# TFG_board_01.net
KiCad netlist of a schematic drawn in EAGLE
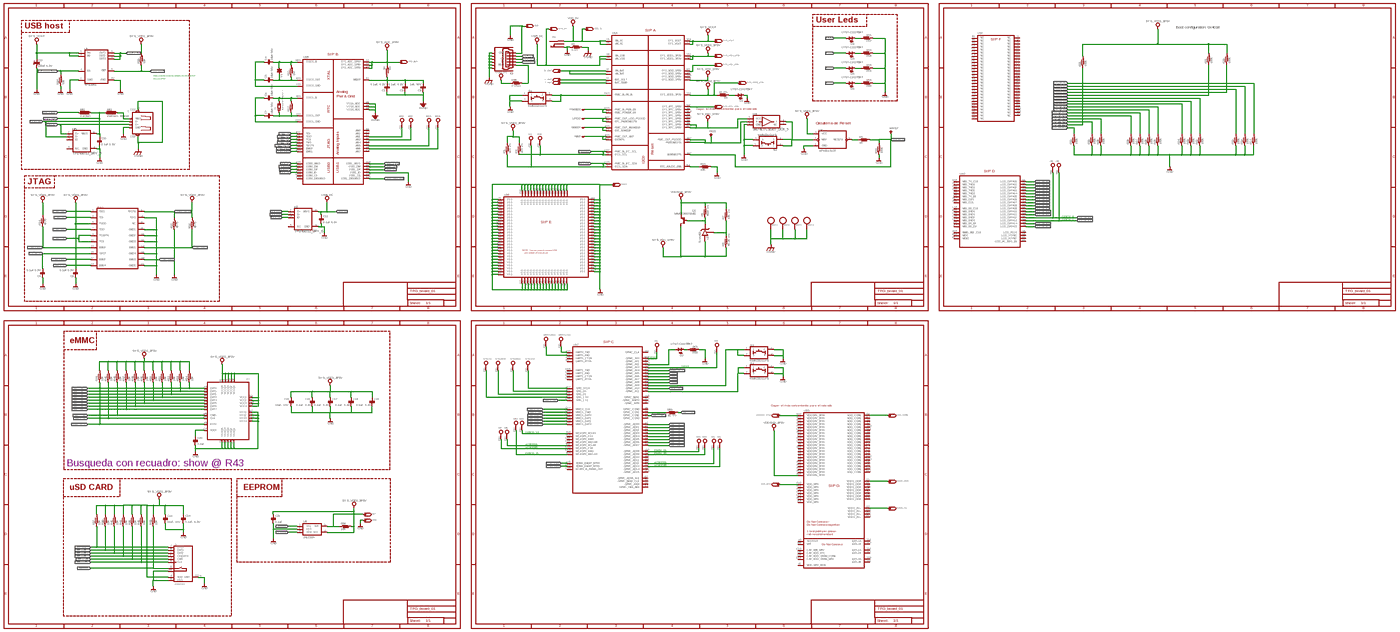
[diagram p0: schematic, sheet 1, overview]
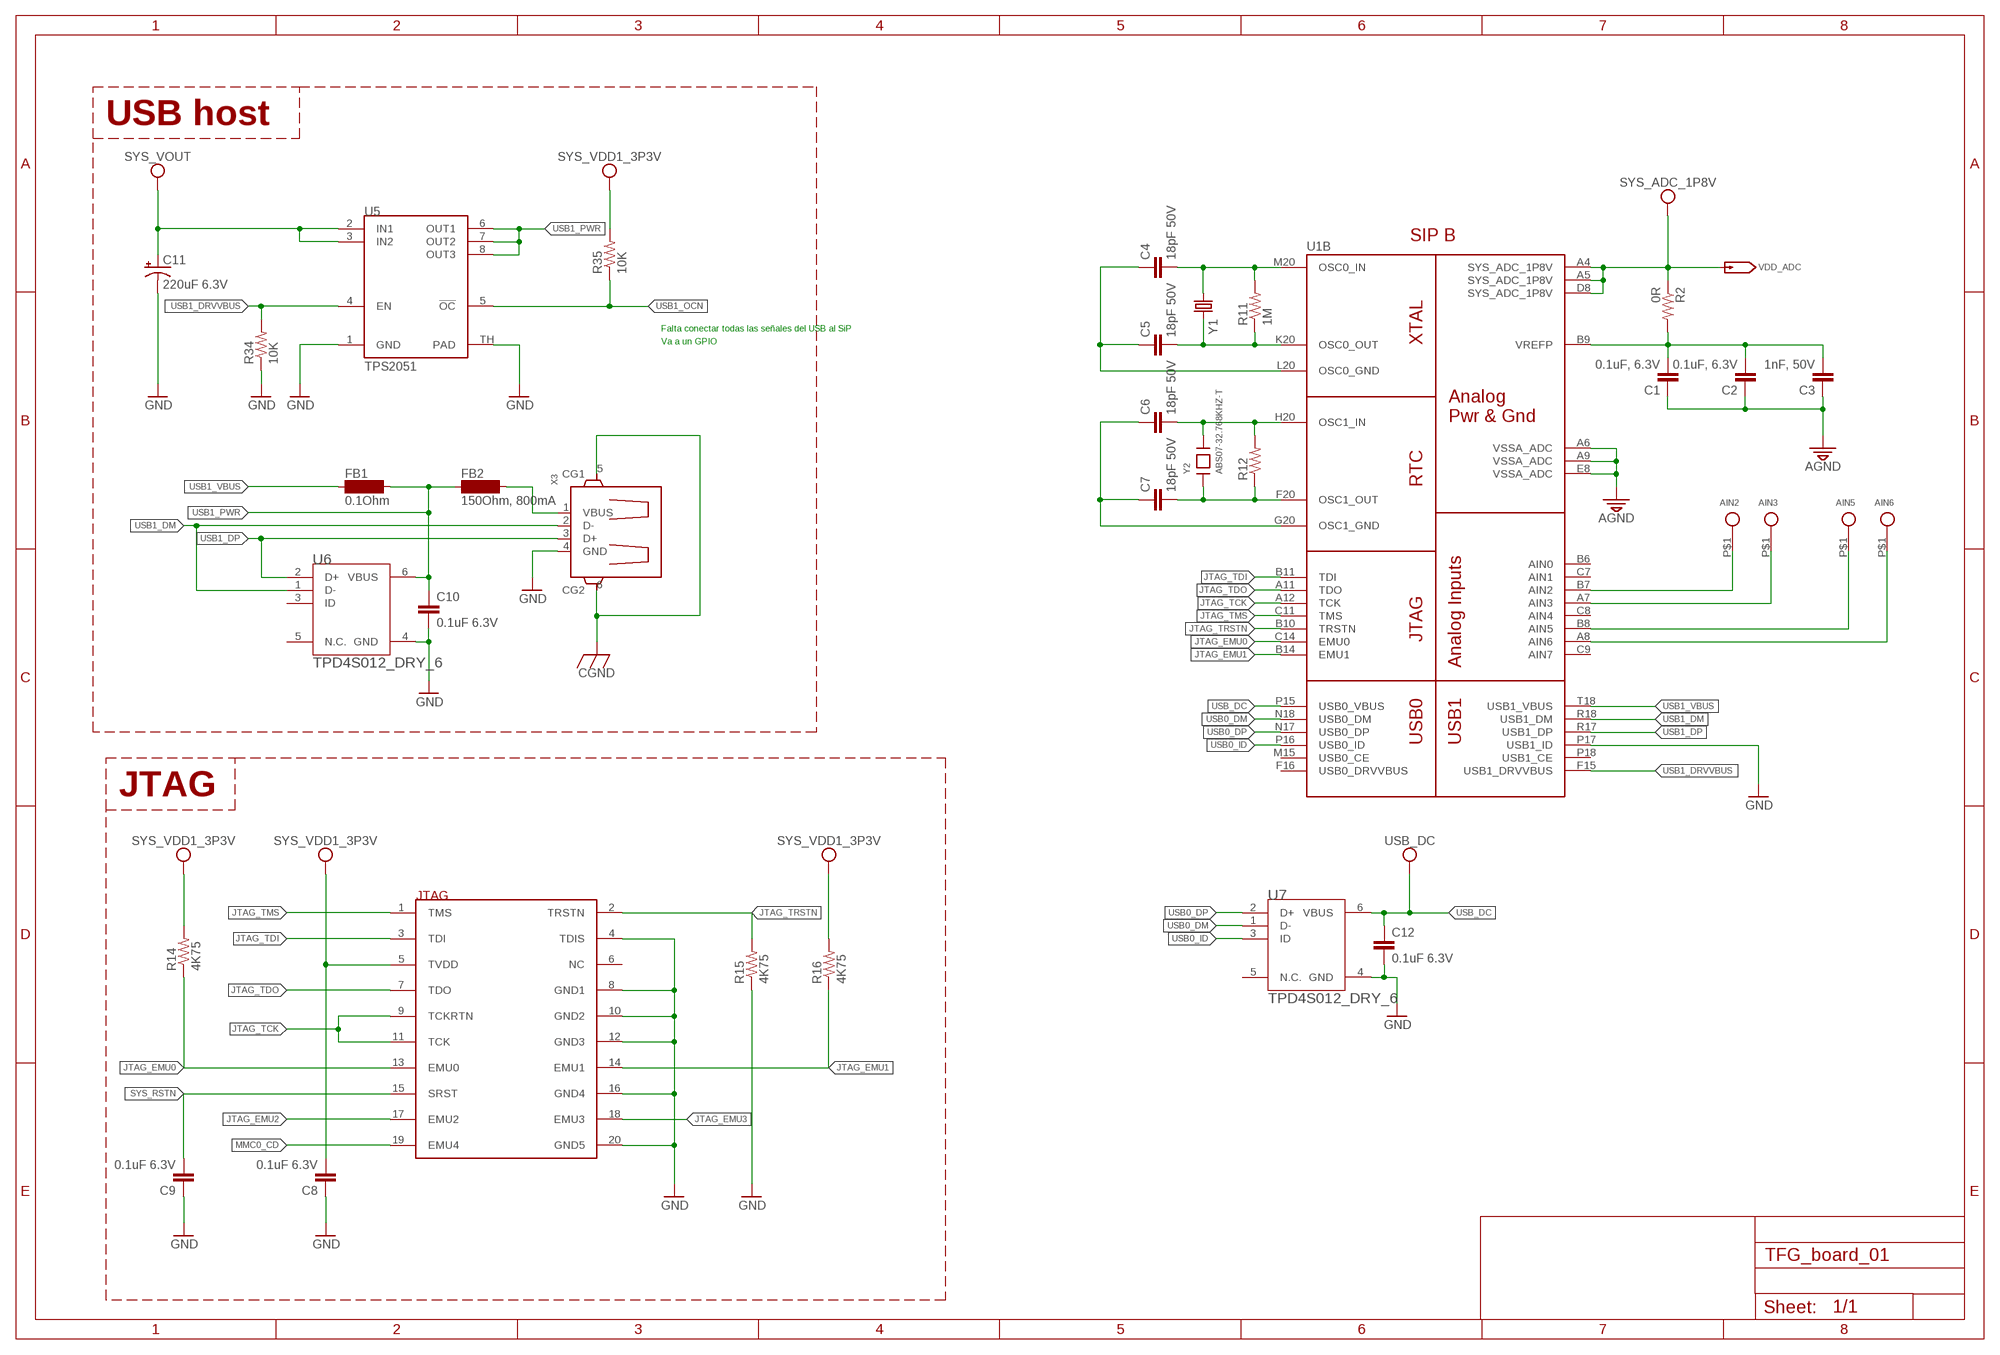
[diagram p1: schematic, sheet 1, part 1 of 7]
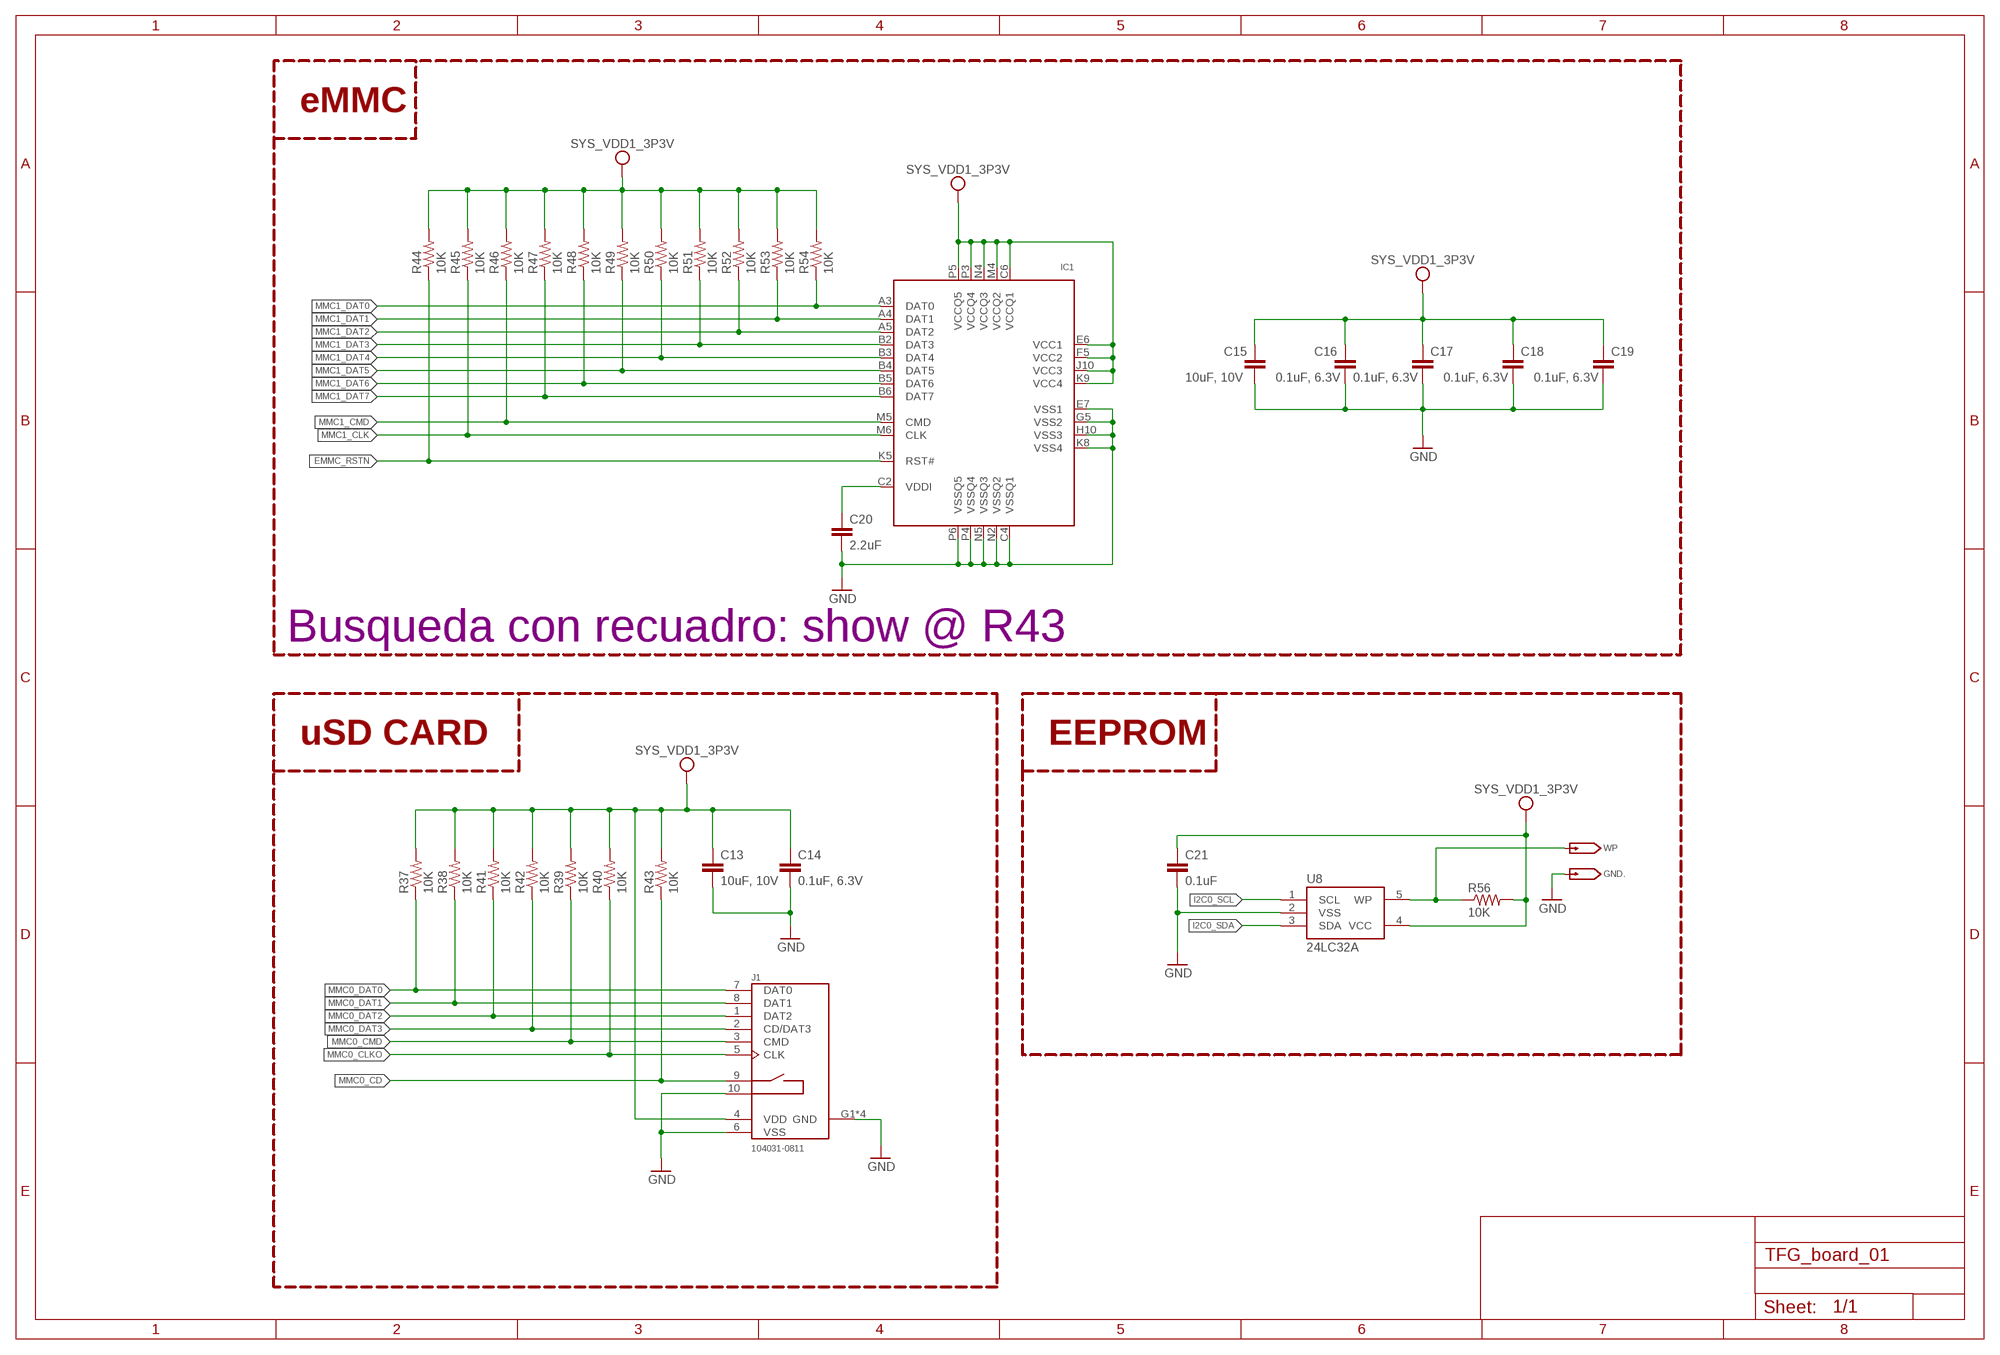
[diagram p2: schematic, sheet 1, part 2 of 7]
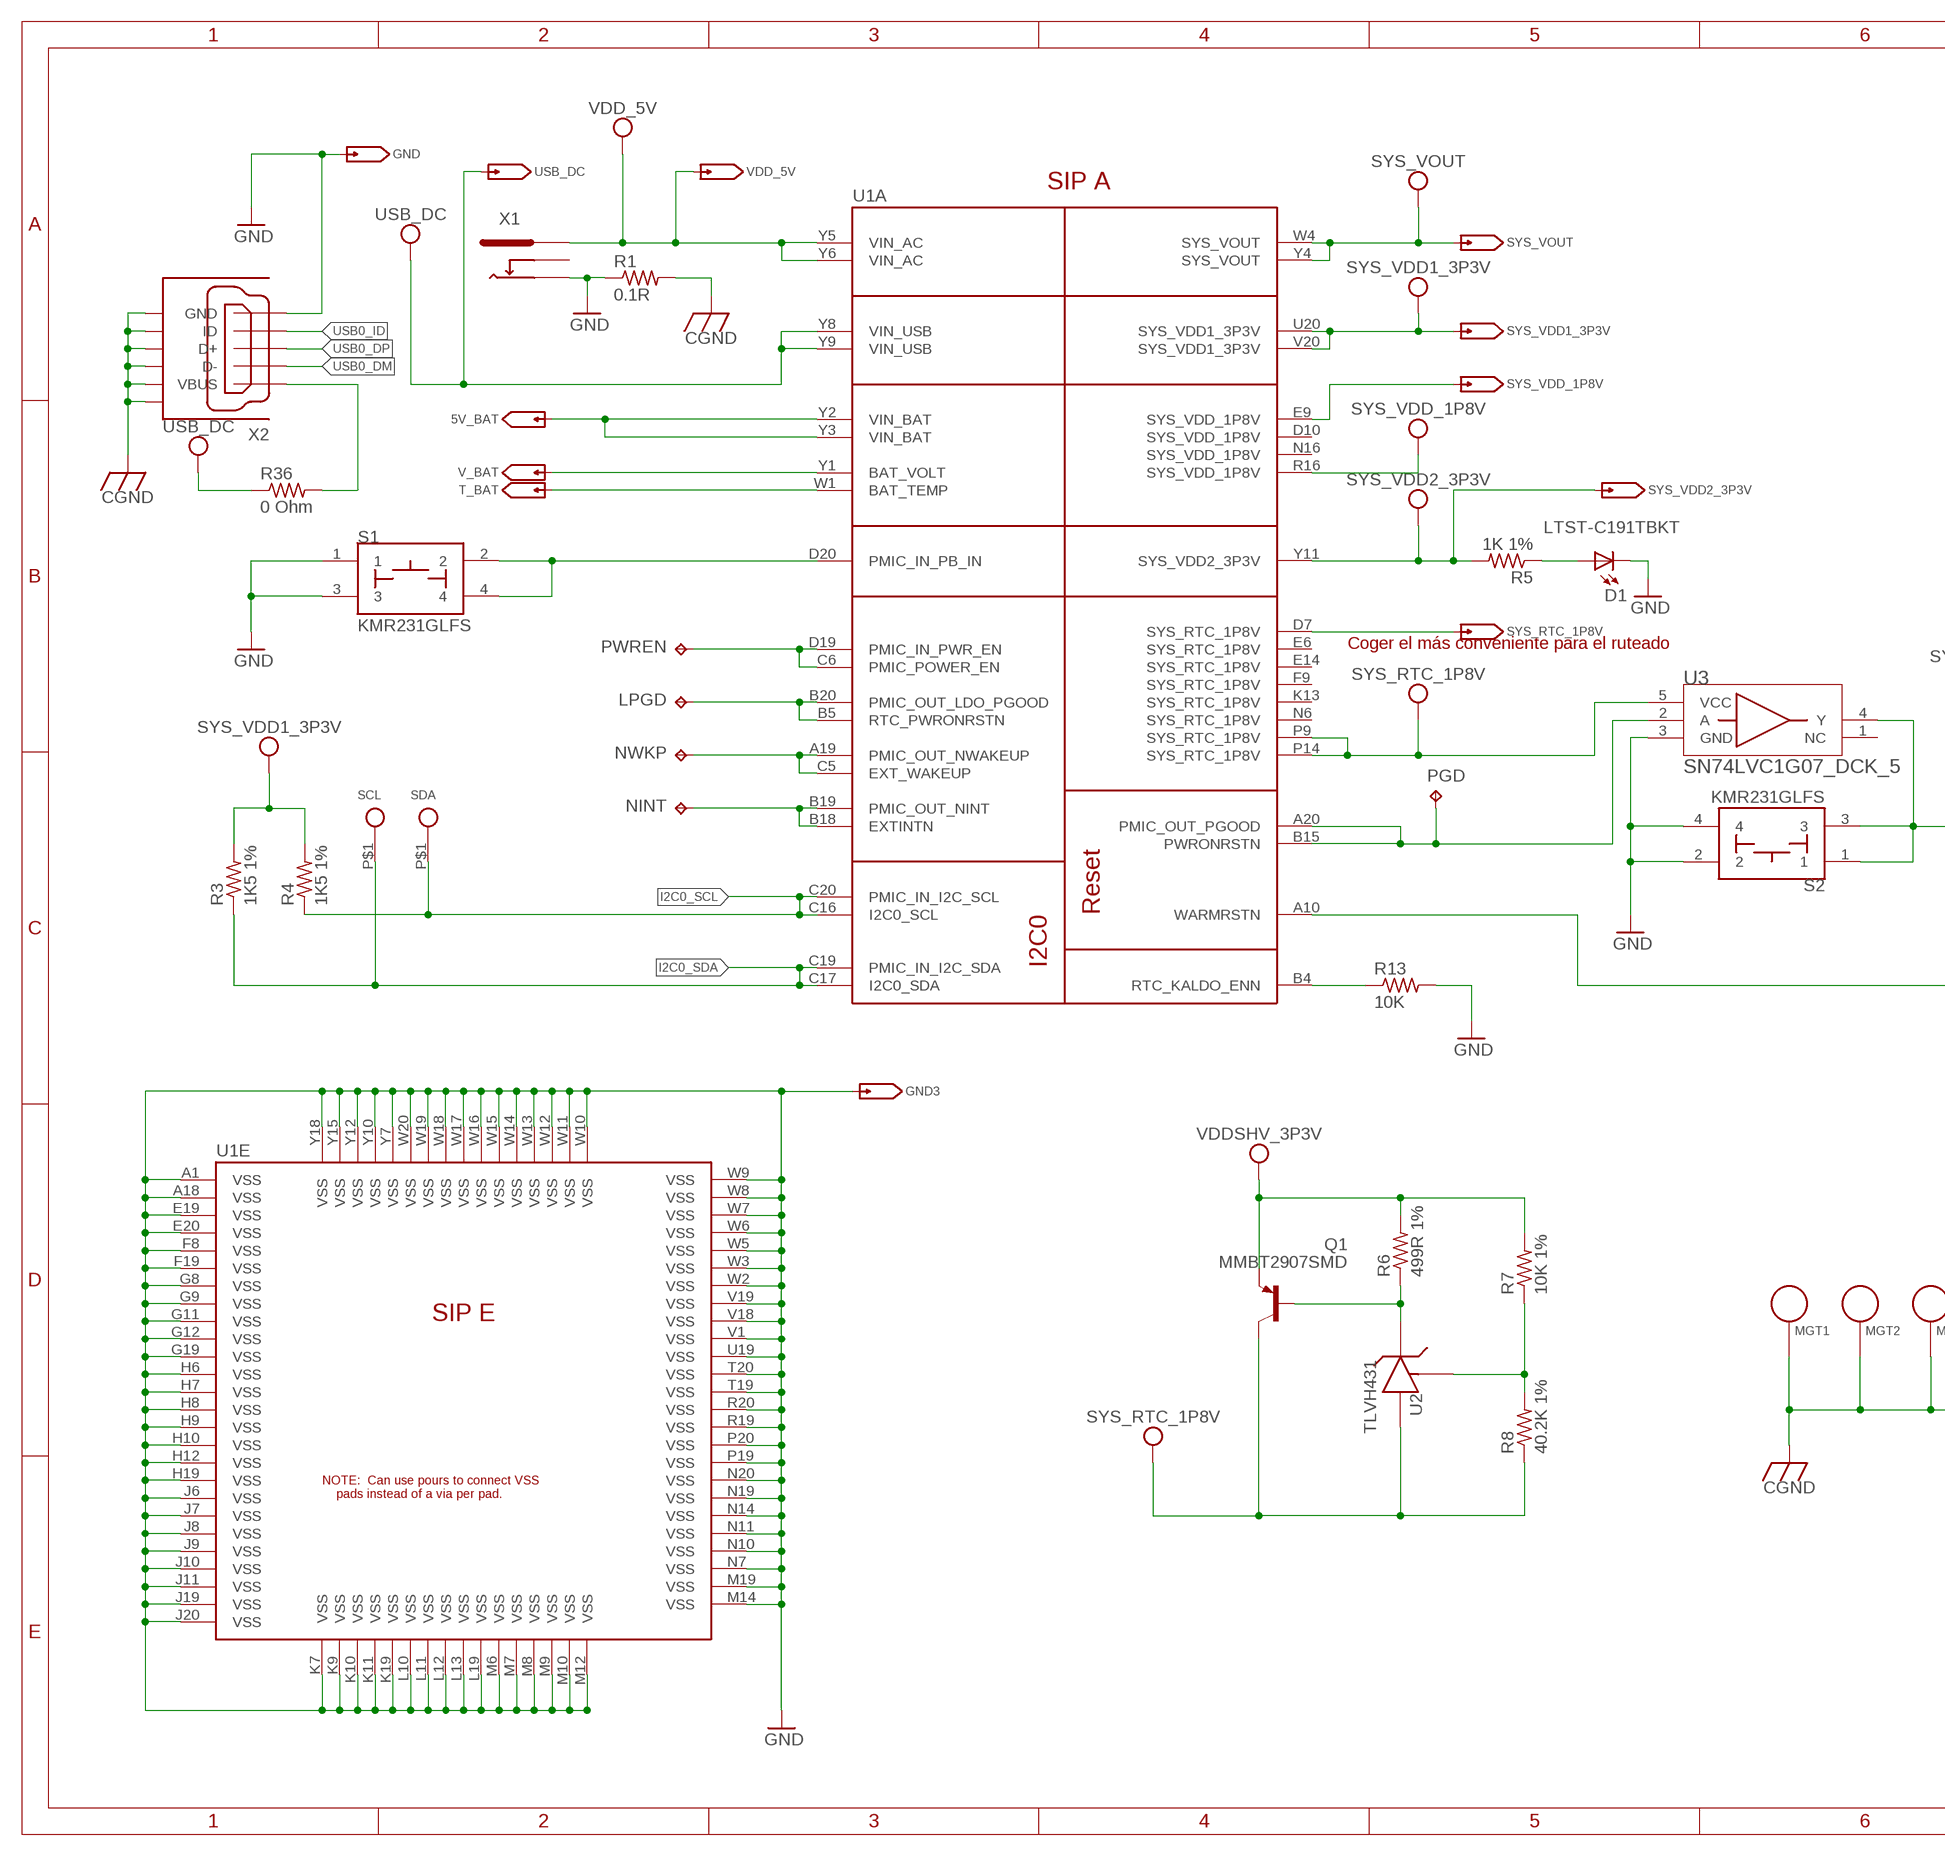
[diagram p3: schematic, sheet 1, part 3 of 7]
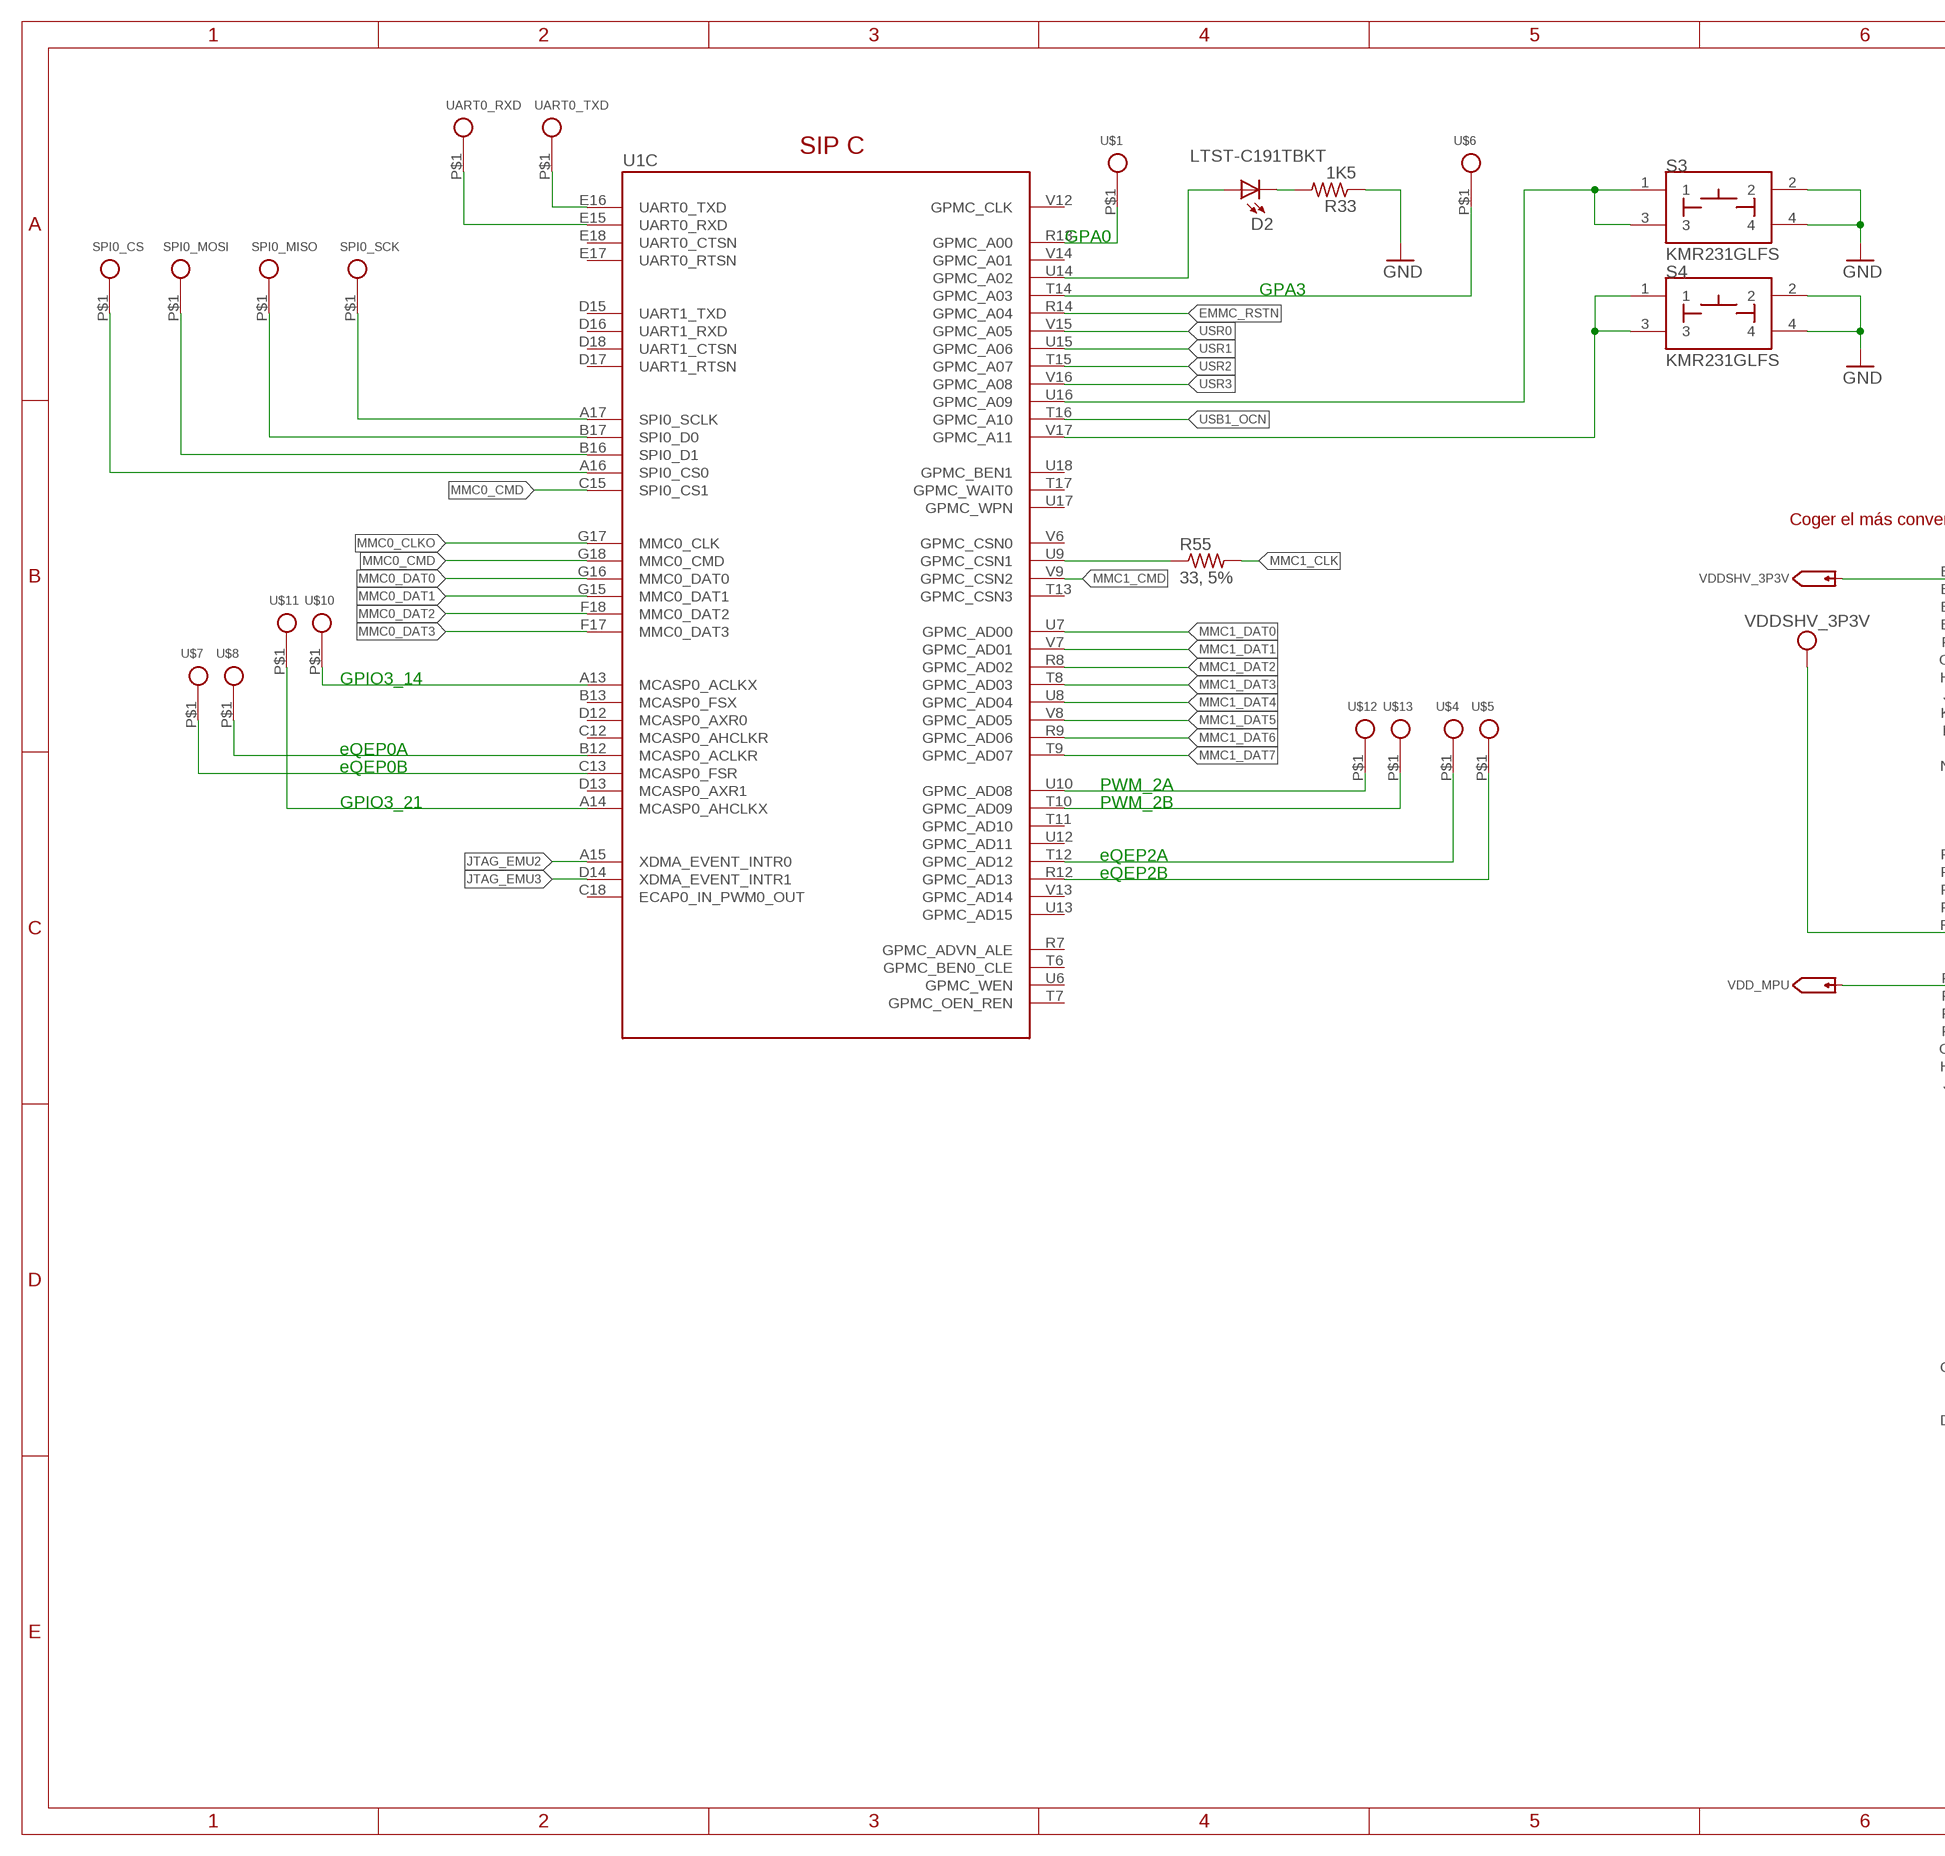
[diagram p4: schematic, sheet 1, part 4 of 7]
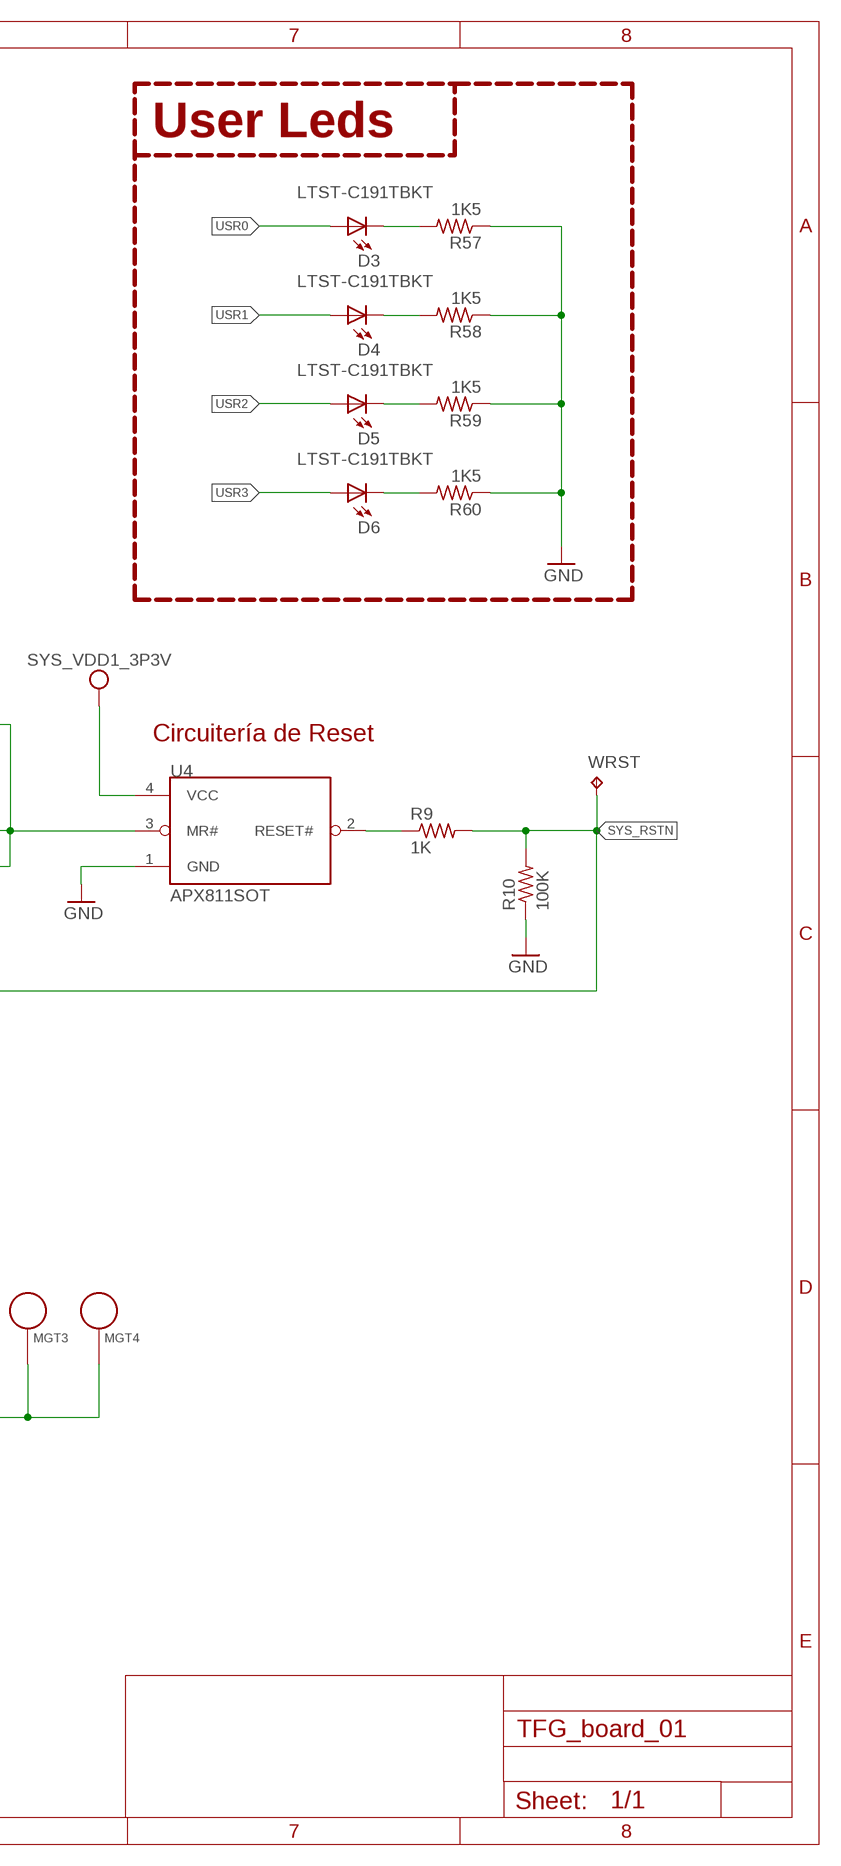
[diagram p5: schematic, sheet 1, part 5 of 7]
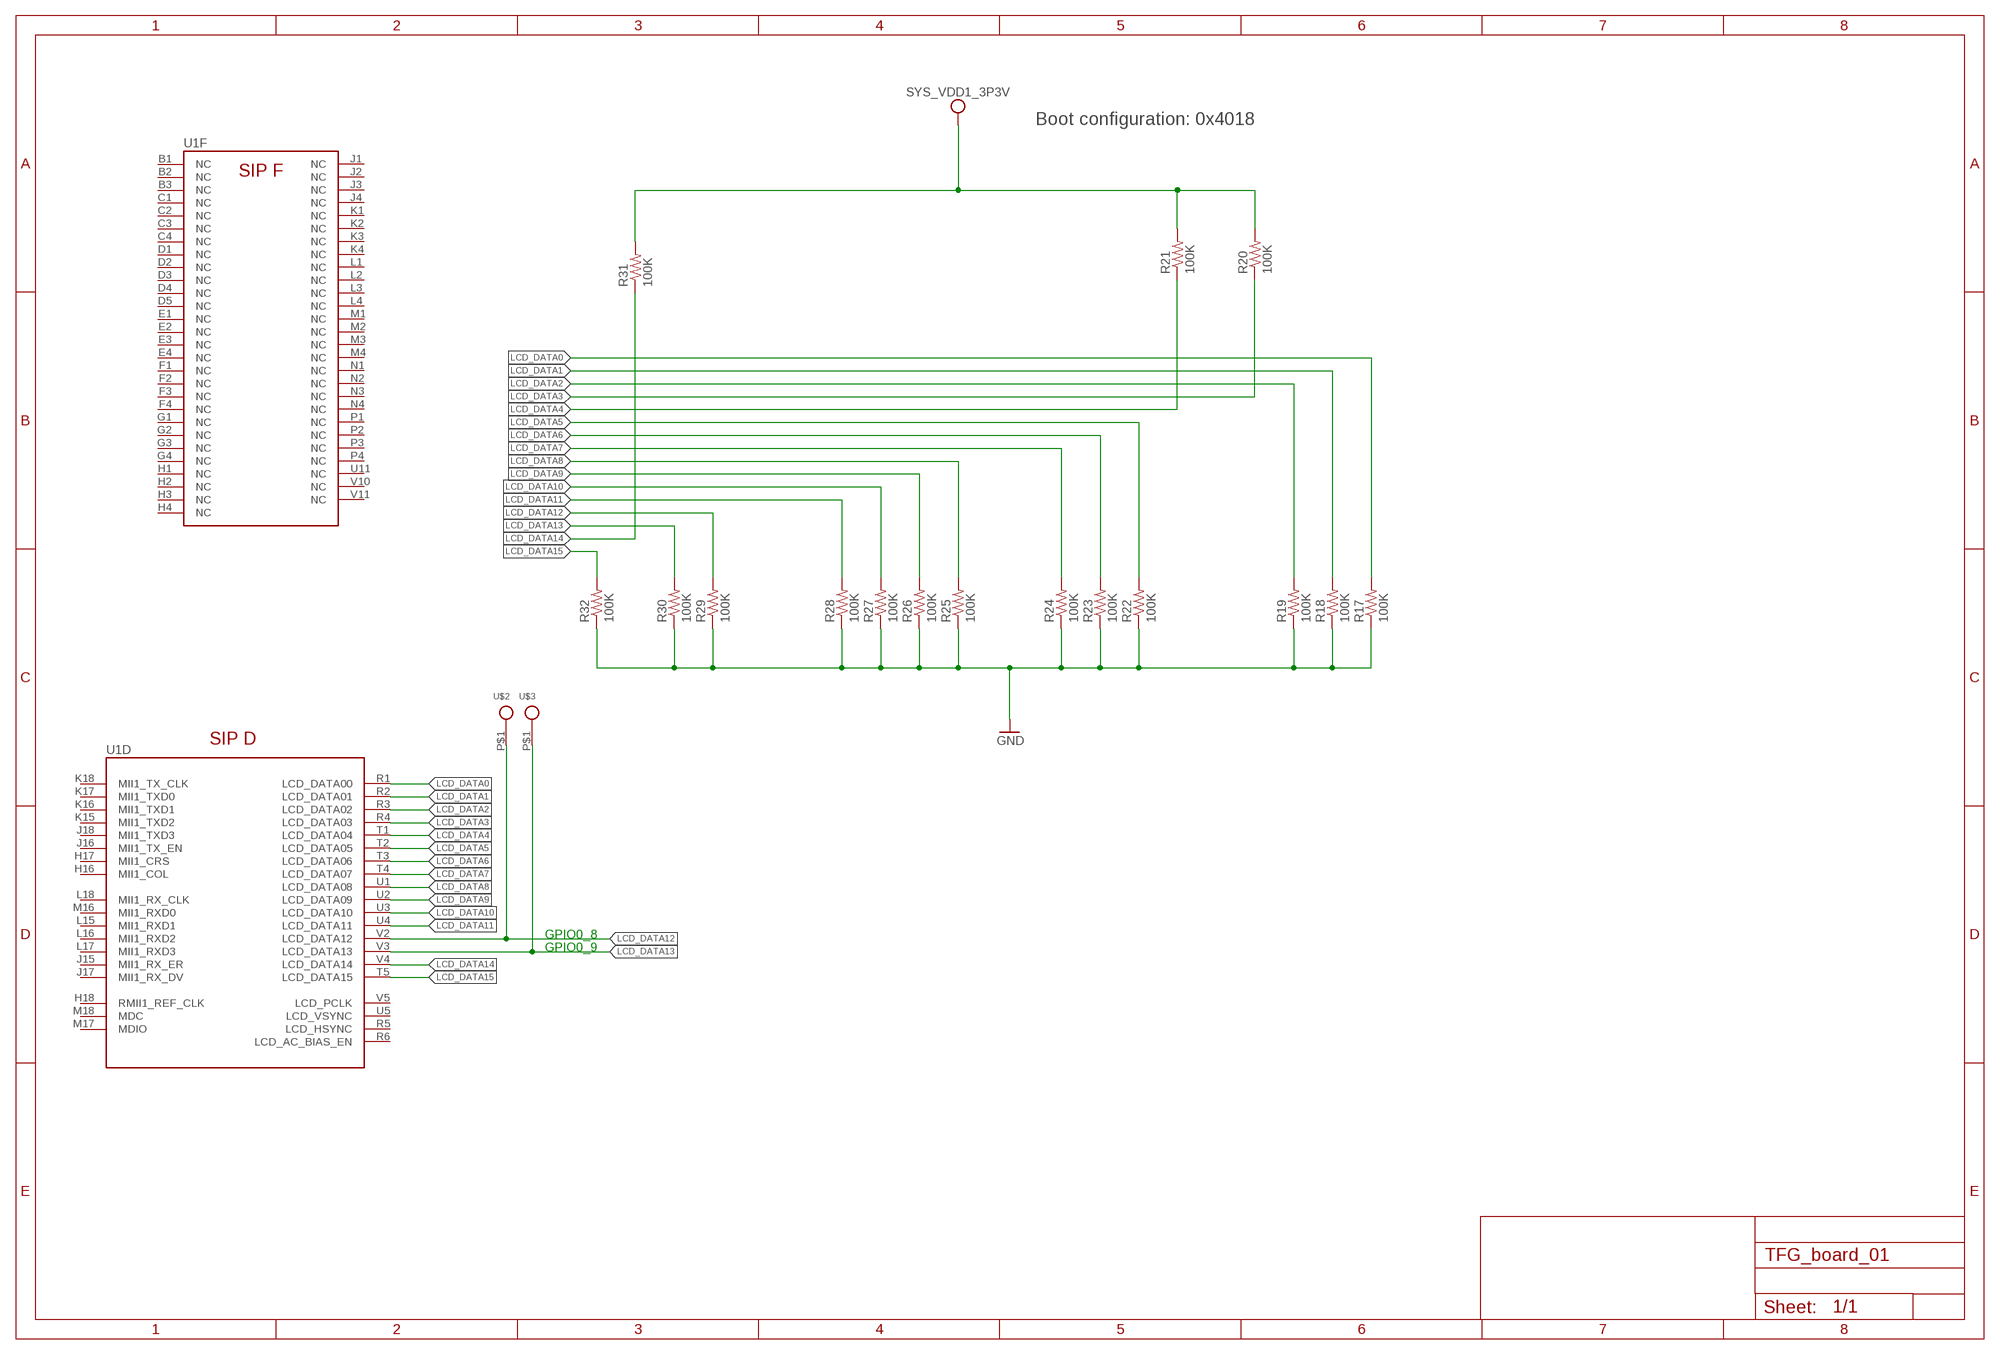
[diagram p6: schematic, sheet 1, part 6 of 7]
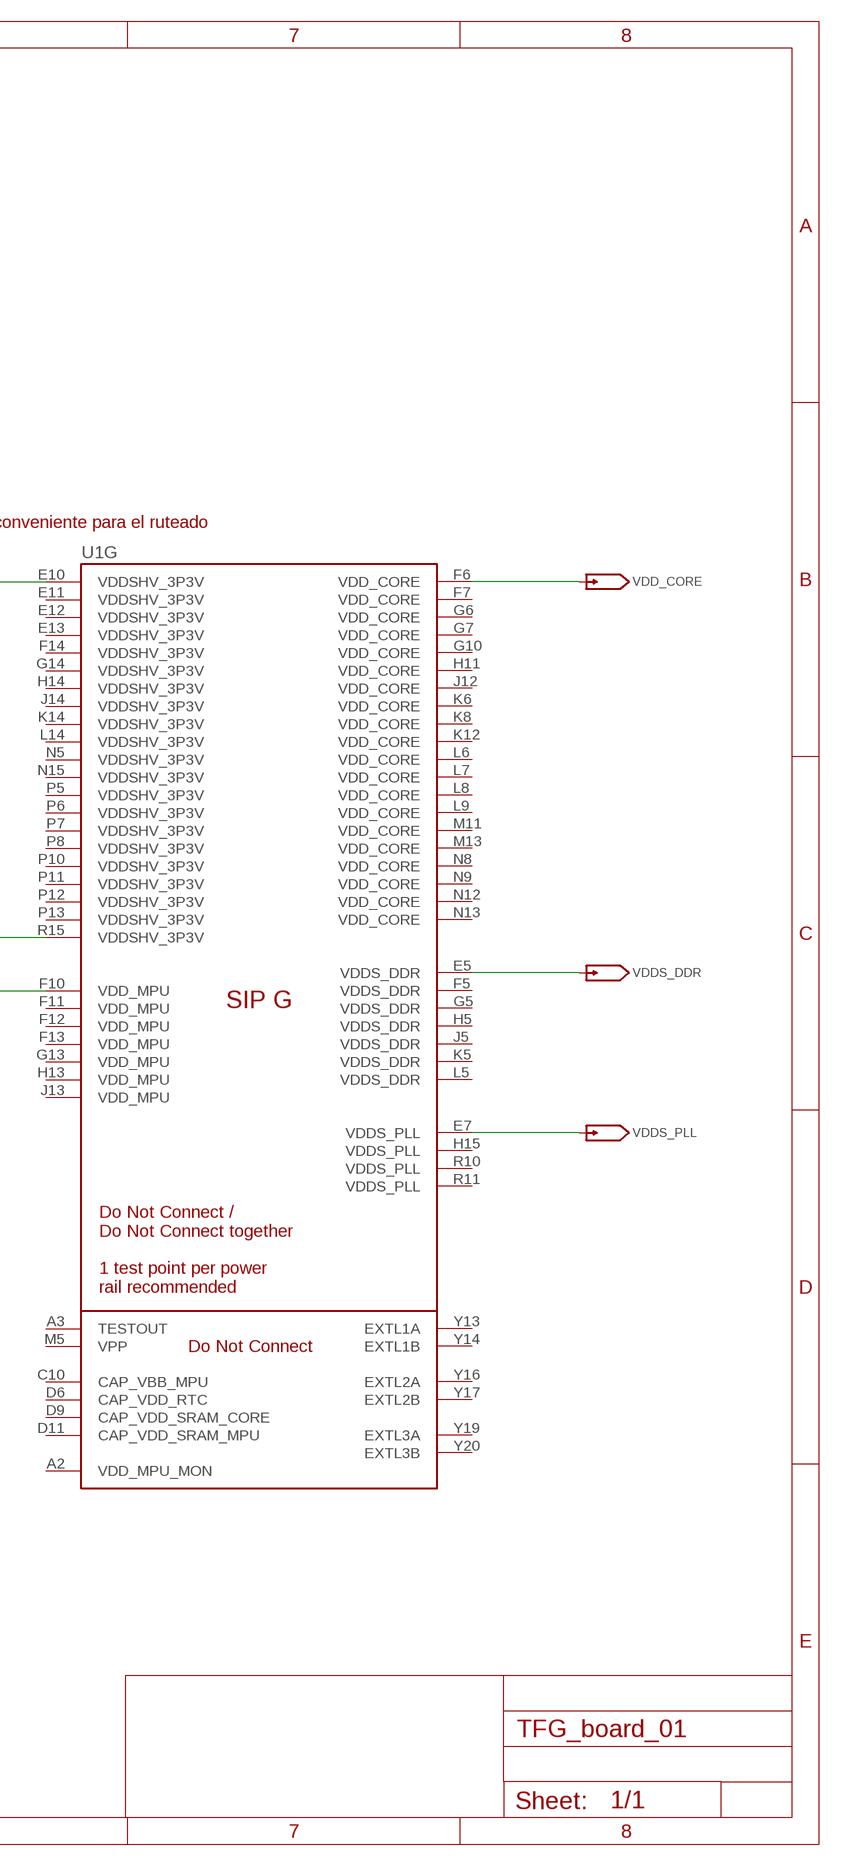
[diagram p7: schematic, sheet 1, part 7 of 7]

(export (version "E")
  (design (tool "Eeschema 10.0.6"))
  (components
    (comp (ref "5V_BAT")
      (value "TESTPAD/W_HOLE_1X1")
      (footprint "eagle-import:TESTPAD_W_HOLE_1X1")
      (libsource (lib "eagle-import") (part "TESTPAD/W_HOLE_1X1"))
    )
    (comp (ref "AIN2")
      (value "HOLE")
      (footprint "eagle-import:HOLE")
      (libsource (lib "eagle-import") (part "HOLE"))
    )
    (comp (ref "AIN3")
      (value "HOLE")
      (footprint "eagle-import:HOLE")
      (libsource (lib "eagle-import") (part "HOLE"))
    )
    (comp (ref "AIN5")
      (value "HOLE")
      (footprint "eagle-import:HOLE")
      (libsource (lib "eagle-import") (part "HOLE"))
    )
    (comp (ref "AIN6")
      (value "HOLE")
      (footprint "eagle-import:HOLE")
      (libsource (lib "eagle-import") (part "HOLE"))
    )
    (comp (ref "C1")
      (value "0.1uF, 6.3V")
      (footprint "eagle-import:C0402")
      (libsource (lib "eagle-import") (part "CC0402"))
    )
    (comp (ref "C2")
      (value "0.1uF, 6.3V")
      (footprint "eagle-import:C0402")
      (libsource (lib "eagle-import") (part "CC0402"))
    )
    (comp (ref "C3")
      (value "1nF, 50V")
      (footprint "eagle-import:C0402")
      (libsource (lib "eagle-import") (part "CC0402"))
    )
    (comp (ref "C4")
      (value "18pF 50V")
      (footprint "eagle-import:C0402")
      (libsource (lib "eagle-import") (part "CC0402"))
    )
    (comp (ref "C5")
      (value "18pF 50V")
      (footprint "eagle-import:C0402")
      (libsource (lib "eagle-import") (part "CC0402"))
    )
    (comp (ref "C6")
      (value "18pF 50V")
      (footprint "eagle-import:C0402")
      (libsource (lib "eagle-import") (part "CC0402"))
    )
    (comp (ref "C7")
      (value "18pF 50V")
      (footprint "eagle-import:C0402")
      (libsource (lib "eagle-import") (part "CC0402"))
    )
    (comp (ref "C8")
      (value "0.1uF 6.3V")
      (footprint "eagle-import:C0402")
      (libsource (lib "eagle-import") (part "CC0402"))
    )
    (comp (ref "C9")
      (value "0.1uF 6.3V")
      (footprint "eagle-import:C0402")
      (libsource (lib "eagle-import") (part "CC0402"))
    )
    (comp (ref "C10")
      (value "0.1uF 6.3V")
      (footprint "eagle-import:C0402")
      (libsource (lib "eagle-import") (part "OSD3358_BAS_RefDesignParts_L2_CC0402"))
    )
    (comp (ref "C11")
      (value "220uF 6.3V")
      (footprint "eagle-import:B_3528-21R")
      (libsource (lib "eagle-import") (part "CPOL-USB/3528-21R"))
    )
    (comp (ref "C12")
      (value "0.1uF 6.3V")
      (footprint "eagle-import:C0402")
      (libsource (lib "eagle-import") (part "OSD3358_BAS_RefDesignParts_L2_CC0402"))
    )
    (comp (ref "C13")
      (value "10uF, 10V")
      (footprint "eagle-import:C0805")
      (libsource (lib "eagle-import") (part "OSD3358_BAS_RefDesignParts_L2_CC0805"))
    )
    (comp (ref "C14")
      (value "0.1uF, 6.3V")
      (footprint "eagle-import:C0402")
      (libsource (lib "eagle-import") (part "OSD3358_BAS_RefDesignParts_L2_CC0402"))
    )
    (comp (ref "C15")
      (value "10uF, 10V")
      (footprint "eagle-import:C0805")
      (libsource (lib "eagle-import") (part "OSD3358_BAS_RefDesignParts_L2_CC0805"))
    )
    (comp (ref "C16")
      (value "0.1uF, 6.3V")
      (footprint "eagle-import:C0402")
      (libsource (lib "eagle-import") (part "OSD3358_BAS_RefDesignParts_L2_CC0402"))
    )
    (comp (ref "C17")
      (value "0.1uF, 6.3V")
      (footprint "eagle-import:C0402")
      (libsource (lib "eagle-import") (part "OSD3358_BAS_RefDesignParts_L2_CC0402"))
    )
    (comp (ref "C18")
      (value "0.1uF, 6.3V")
      (footprint "eagle-import:C0402")
      (libsource (lib "eagle-import") (part "OSD3358_BAS_RefDesignParts_L2_CC0402"))
    )
    (comp (ref "C19")
      (value "0.1uF, 6.3V")
      (footprint "eagle-import:C0402")
      (libsource (lib "eagle-import") (part "OSD3358_BAS_RefDesignParts_L2_CC0402"))
    )
    (comp (ref "C20")
      (value "2.2uF")
      (footprint "eagle-import:C0402")
      (libsource (lib "eagle-import") (part "OSD3358_BAS_RefDesignParts_L2_CC0402"))
    )
    (comp (ref "C21")
      (value "0.1uF")
      (footprint "eagle-import:C0402")
      (libsource (lib "eagle-import") (part "OSD3358_BAS_RefDesignParts_L2_CC0402"))
    )
    (comp (ref "D1")
      (value "LTST-C191TBKT")
      (footprint "eagle-import:EIA-STD")
      (libsource (lib "eagle-import") (part "LTST-C191TBKTLED_EIA-STD"))
    )
    (comp (ref "D2")
      (value "LTST-C191TBKT")
      (footprint "eagle-import:EIA-STD")
      (libsource (lib "eagle-import") (part "LTST-C191TBKTLED_EIA-STD"))
    )
    (comp (ref "D3")
      (value "LTST-C191TBKT")
      (footprint "eagle-import:EIA-STD")
      (libsource (lib "eagle-import") (part "LTST-C191TBKTLED_EIA-STD"))
    )
    (comp (ref "D4")
      (value "LTST-C191TBKT")
      (footprint "eagle-import:EIA-STD")
      (libsource (lib "eagle-import") (part "LTST-C191TBKTLED_EIA-STD"))
    )
    (comp (ref "D5")
      (value "LTST-C191TBKT")
      (footprint "eagle-import:EIA-STD")
      (libsource (lib "eagle-import") (part "LTST-C191TBKTLED_EIA-STD"))
    )
    (comp (ref "D6")
      (value "LTST-C191TBKT")
      (footprint "eagle-import:EIA-STD")
      (libsource (lib "eagle-import") (part "LTST-C191TBKTLED_EIA-STD"))
    )
    (comp (ref "FB1")
      (value "0.1Ohm")
      (footprint "eagle-import:C0805")
      (libsource (lib "eagle-import") (part "MPZ2012S601AT000FB_0805"))
    )
    (comp (ref "FB2")
      (value "150Ohm, 800mA")
      (footprint "eagle-import:C0805")
      (libsource (lib "eagle-import") (part "MPZ2012S601AT000FB_0805"))
    )
    (comp (ref "GND")
      (value "TESTPAD/W_HOLE_1X1")
      (footprint "eagle-import:TESTPAD_W_HOLE_1X1")
      (libsource (lib "eagle-import") (part "TESTPAD/W_HOLE_1X1"))
    )
    (comp (ref "GND.")
      (value "TESTPAD/W_HOLE_1X1")
      (footprint "eagle-import:TESTPAD_W_HOLE_1X1")
      (libsource (lib "eagle-import") (part "OSD3358_BAS_RefDesignParts_L2_TESTPAD/W_HOLE_1X1"))
    )
    (comp (ref "GND3")
      (value "TESTPAD/W_HOLE_1X1")
      (footprint "eagle-import:TESTPAD_W_HOLE_1X1")
      (libsource (lib "eagle-import") (part "TESTPAD/W_HOLE_1X1"))
    )
    (comp (ref "IC1")
      (value "EMMC04G-S100-B08U")
      (footprint "eagle-import:MICRON_EMMC_153")
      (libsource (lib "eagle-import") (part "EMMC04G-S100-B08U"))
    )
    (comp (ref "J1")
      (value "104031-0811")
      (footprint "eagle-import:MOLEX_104031-0811")
      (fields (field (name "MF") "Molex, LLC"))
      (libsource (lib "eagle-import") (part "104031-0811"))
    )
    (comp (ref "JTAG")
      (value "CTI-JTAG")
      (footprint "eagle-import:CTI-JTAG")
      (libsource (lib "eagle-import") (part "CTI-JTAG"))
    )
    (comp (ref "LPGD")
      (value "TPTP15R")
      (footprint "eagle-import:TP15R")
      (libsource (lib "eagle-import") (part "TPTP15R"))
    )
    (comp (ref "MGT1")
      (value "MOUNTING_HOLE")
      (footprint "eagle-import:MOUNTING_HOLE")
      (libsource (lib "eagle-import") (part "MOUNTING_HOLE"))
    )
    (comp (ref "MGT2")
      (value "MOUNTING_HOLE")
      (footprint "eagle-import:MOUNTING_HOLE")
      (libsource (lib "eagle-import") (part "MOUNTING_HOLE"))
    )
    (comp (ref "MGT3")
      (value "MOUNTING_HOLE")
      (footprint "eagle-import:MOUNTING_HOLE")
      (libsource (lib "eagle-import") (part "MOUNTING_HOLE"))
    )
    (comp (ref "MGT4")
      (value "MOUNTING_HOLE")
      (footprint "eagle-import:MOUNTING_HOLE")
      (libsource (lib "eagle-import") (part "MOUNTING_HOLE"))
    )
    (comp (ref "NINT")
      (value "TPTP15R")
      (footprint "eagle-import:TP15R")
      (libsource (lib "eagle-import") (part "TPTP15R"))
    )
    (comp (ref "NWKP")
      (value "TPTP15R")
      (footprint "eagle-import:TP15R")
      (libsource (lib "eagle-import") (part "TPTP15R"))
    )
    (comp (ref "PGD")
      (value "TPTP15R")
      (footprint "eagle-import:TP15R")
      (libsource (lib "eagle-import") (part "TPTP15R"))
    )
    (comp (ref "PWREN")
      (value "TPTP15R")
      (footprint "eagle-import:TP15R")
      (libsource (lib "eagle-import") (part "TPTP15R"))
    )
    (comp (ref "Q1")
      (value "MMBT2907SMD")
      (footprint "eagle-import:SOT23-BEC")
      (libsource (lib "eagle-import") (part "MMBT2907SMD"))
    )
    (comp (ref "R1")
      (value "0.1R")
      (footprint "eagle-import:R0805")
      (libsource (lib "eagle-import") (part "R-US_R0805"))
    )
    (comp (ref "R2")
      (value "0R")
      (footprint "eagle-import:R0402")
      (libsource (lib "eagle-import") (part "R-US_R0402"))
    )
    (comp (ref "R3")
      (value "1K5 1%")
      (footprint "eagle-import:R0402")
      (libsource (lib "eagle-import") (part "R-US_R0402"))
    )
    (comp (ref "R4")
      (value "1K5 1%")
      (footprint "eagle-import:R0402")
      (libsource (lib "eagle-import") (part "R-US_R0402"))
    )
    (comp (ref "R5")
      (value "1K 1%")
      (footprint "eagle-import:R0402")
      (libsource (lib "eagle-import") (part "R-US_R0402"))
    )
    (comp (ref "R6")
      (value "499R 1%")
      (footprint "eagle-import:R0402")
      (libsource (lib "eagle-import") (part "R-US_R0402"))
    )
    (comp (ref "R7")
      (value "10K 1%")
      (footprint "eagle-import:R0402")
      (libsource (lib "eagle-import") (part "R-US_R0402"))
    )
    (comp (ref "R8")
      (value "40.2K 1%")
      (footprint "eagle-import:R0402")
      (libsource (lib "eagle-import") (part "R-US_R0402"))
    )
    (comp (ref "R9")
      (value "1K")
      (footprint "eagle-import:R0402")
      (libsource (lib "eagle-import") (part "R-US_R0402"))
    )
    (comp (ref "R10")
      (value "100K")
      (footprint "eagle-import:R0402")
      (libsource (lib "eagle-import") (part "R-US_R0402"))
    )
    (comp (ref "R11")
      (value "1M")
      (footprint "eagle-import:R0402")
      (libsource (lib "eagle-import") (part "R-US_R0402"))
    )
    (comp (ref "R12")
      (value "R-US_R0402")
      (footprint "eagle-import:R0402")
      (libsource (lib "eagle-import") (part "R-US_R0402"))
    )
    (comp (ref "R13")
      (value "10K")
      (footprint "eagle-import:R0402")
      (libsource (lib "eagle-import") (part "R-US_R0402"))
    )
    (comp (ref "R14")
      (value "4K75")
      (footprint "eagle-import:R0402")
      (libsource (lib "eagle-import") (part "R-US_R0402"))
    )
    (comp (ref "R15")
      (value "4K75")
      (footprint "eagle-import:R0402")
      (libsource (lib "eagle-import") (part "R-US_R0402"))
    )
    (comp (ref "R16")
      (value "4K75")
      (footprint "eagle-import:R0402")
      (libsource (lib "eagle-import") (part "R-US_R0402"))
    )
    (comp (ref "R17")
      (value "100K")
      (footprint "eagle-import:R0402")
      (libsource (lib "eagle-import") (part "R-US_R0402"))
    )
    (comp (ref "R18")
      (value "100K")
      (footprint "eagle-import:R0402")
      (libsource (lib "eagle-import") (part "R-US_R0402"))
    )
    (comp (ref "R19")
      (value "100K")
      (footprint "eagle-import:R0402")
      (libsource (lib "eagle-import") (part "R-US_R0402"))
    )
    (comp (ref "R20")
      (value "100K")
      (footprint "eagle-import:R0402")
      (libsource (lib "eagle-import") (part "R-US_R0402"))
    )
    (comp (ref "R21")
      (value "100K")
      (footprint "eagle-import:R0402")
      (libsource (lib "eagle-import") (part "R-US_R0402"))
    )
    (comp (ref "R22")
      (value "100K")
      (footprint "eagle-import:R0402")
      (libsource (lib "eagle-import") (part "R-US_R0402"))
    )
    (comp (ref "R23")
      (value "100K")
      (footprint "eagle-import:R0402")
      (libsource (lib "eagle-import") (part "R-US_R0402"))
    )
    (comp (ref "R24")
      (value "100K")
      (footprint "eagle-import:R0402")
      (libsource (lib "eagle-import") (part "R-US_R0402"))
    )
    (comp (ref "R25")
      (value "100K")
      (footprint "eagle-import:R0402")
      (libsource (lib "eagle-import") (part "R-US_R0402"))
    )
    (comp (ref "R26")
      (value "100K")
      (footprint "eagle-import:R0402")
      (libsource (lib "eagle-import") (part "R-US_R0402"))
    )
    (comp (ref "R27")
      (value "100K")
      (footprint "eagle-import:R0402")
      (libsource (lib "eagle-import") (part "R-US_R0402"))
    )
    (comp (ref "R28")
      (value "100K")
      (footprint "eagle-import:R0402")
      (libsource (lib "eagle-import") (part "R-US_R0402"))
    )
    (comp (ref "R29")
      (value "100K")
      (footprint "eagle-import:R0402")
      (libsource (lib "eagle-import") (part "R-US_R0402"))
    )
    (comp (ref "R30")
      (value "100K")
      (footprint "eagle-import:R0402")
      (libsource (lib "eagle-import") (part "R-US_R0402"))
    )
    (comp (ref "R31")
      (value "100K")
      (footprint "eagle-import:R0402")
      (libsource (lib "eagle-import") (part "R-US_R0402"))
    )
    (comp (ref "R32")
      (value "100K")
      (footprint "eagle-import:R0402")
      (libsource (lib "eagle-import") (part "R-US_R0402"))
    )
    (comp (ref "R33")
      (value "1K5")
      (footprint "eagle-import:R0402")
      (libsource (lib "eagle-import") (part "R-US_R0402"))
    )
    (comp (ref "R34")
      (value "10K")
      (footprint "eagle-import:R0402")
      (libsource (lib "eagle-import") (part "OSD3358_BAS_RefDesignParts_L2_R-US_R0402"))
    )
    (comp (ref "R35")
      (value "10K")
      (footprint "eagle-import:R0402")
      (libsource (lib "eagle-import") (part "OSD3358_BAS_RefDesignParts_L2_R-US_R0402"))
    )
    (comp (ref "R36")
      (value "0 Ohm")
      (footprint "eagle-import:R0805")
      (libsource (lib "eagle-import") (part "R-US_R0805"))
    )
    (comp (ref "R37")
      (value "10K")
      (footprint "eagle-import:R0402")
      (libsource (lib "eagle-import") (part "R-US_R0402"))
    )
    (comp (ref "R38")
      (value "10K")
      (footprint "eagle-import:R0402")
      (libsource (lib "eagle-import") (part "R-US_R0402"))
    )
    (comp (ref "R39")
      (value "10K")
      (footprint "eagle-import:R0402")
      (libsource (lib "eagle-import") (part "R-US_R0402"))
    )
    (comp (ref "R40")
      (value "10K")
      (footprint "eagle-import:R0402")
      (libsource (lib "eagle-import") (part "R-US_R0402"))
    )
    (comp (ref "R41")
      (value "10K")
      (footprint "eagle-import:R0402")
      (libsource (lib "eagle-import") (part "R-US_R0402"))
    )
    (comp (ref "R42")
      (value "10K")
      (footprint "eagle-import:R0402")
      (libsource (lib "eagle-import") (part "R-US_R0402"))
    )
    (comp (ref "R43")
      (value "10K")
      (footprint "eagle-import:R0402")
      (libsource (lib "eagle-import") (part "R-US_R0402"))
    )
    (comp (ref "R44")
      (value "10K")
      (footprint "eagle-import:R0402")
      (libsource (lib "eagle-import") (part "OSD3358_BAS_RefDesignParts_L2_R-US_R0402"))
    )
    (comp (ref "R45")
      (value "10K")
      (footprint "eagle-import:R0402")
      (libsource (lib "eagle-import") (part "OSD3358_BAS_RefDesignParts_L2_R-US_R0402"))
    )
    (comp (ref "R46")
      (value "10K")
      (footprint "eagle-import:R0402")
      (libsource (lib "eagle-import") (part "OSD3358_BAS_RefDesignParts_L2_R-US_R0402"))
    )
    (comp (ref "R47")
      (value "10K")
      (footprint "eagle-import:R0402")
      (libsource (lib "eagle-import") (part "OSD3358_BAS_RefDesignParts_L2_R-US_R0402"))
    )
    (comp (ref "R48")
      (value "10K")
      (footprint "eagle-import:R0402")
      (libsource (lib "eagle-import") (part "OSD3358_BAS_RefDesignParts_L2_R-US_R0402"))
    )
    (comp (ref "R49")
      (value "10K")
      (footprint "eagle-import:R0402")
      (libsource (lib "eagle-import") (part "OSD3358_BAS_RefDesignParts_L2_R-US_R0402"))
    )
    (comp (ref "R50")
      (value "10K")
      (footprint "eagle-import:R0402")
      (libsource (lib "eagle-import") (part "OSD3358_BAS_RefDesignParts_L2_R-US_R0402"))
    )
    (comp (ref "R51")
      (value "10K")
      (footprint "eagle-import:R0402")
      (libsource (lib "eagle-import") (part "OSD3358_BAS_RefDesignParts_L2_R-US_R0402"))
    )
    (comp (ref "R52")
      (value "10K")
      (footprint "eagle-import:R0402")
      (libsource (lib "eagle-import") (part "OSD3358_BAS_RefDesignParts_L2_R-US_R0402"))
    )
    (comp (ref "R53")
      (value "10K")
      (footprint "eagle-import:R0402")
      (libsource (lib "eagle-import") (part "OSD3358_BAS_RefDesignParts_L2_R-US_R0402"))
    )
    (comp (ref "R54")
      (value "10K")
      (footprint "eagle-import:R0402")
      (libsource (lib "eagle-import") (part "OSD3358_BAS_RefDesignParts_L2_R-US_R0402"))
    )
    (comp (ref "R55")
      (value "33, 5%")
      (footprint "eagle-import:R0402")
      (libsource (lib "eagle-import") (part "OSD3358_BAS_RefDesignParts_L2_R-US_R0402"))
    )
    (comp (ref "R56")
      (value "10K")
      (footprint "eagle-import:R0402")
      (libsource (lib "eagle-import") (part "OSD3358_BAS_RefDesignParts_L2_R-US_R0402"))
    )
    (comp (ref "R57")
      (value "1K5")
      (footprint "eagle-import:R0402")
      (libsource (lib "eagle-import") (part "R-US_R0402"))
    )
    (comp (ref "R58")
      (value "1K5")
      (footprint "eagle-import:R0402")
      (libsource (lib "eagle-import") (part "R-US_R0402"))
    )
    (comp (ref "R59")
      (value "1K5")
      (footprint "eagle-import:R0402")
      (libsource (lib "eagle-import") (part "R-US_R0402"))
    )
    (comp (ref "R60")
      (value "1K5")
      (footprint "eagle-import:R0402")
      (libsource (lib "eagle-import") (part "R-US_R0402"))
    )
    (comp (ref "S1")
      (value "KMR231GLFS")
      (footprint "eagle-import:SW4SMD_63X161LS")
      (libsource (lib "eagle-import") (part "KMR231GLFS"))
    )
    (comp (ref "S2")
      (value "KMR231GLFS")
      (footprint "eagle-import:SW4SMD_63X161LS")
      (libsource (lib "eagle-import") (part "KMR231GLFS"))
    )
    (comp (ref "S3")
      (value "KMR231GLFS")
      (footprint "eagle-import:SW4SMD_63X161LS")
      (libsource (lib "eagle-import") (part "KMR231GLFS"))
    )
    (comp (ref "S4")
      (value "KMR231GLFS")
      (footprint "eagle-import:SW4SMD_63X161LS")
      (libsource (lib "eagle-import") (part "KMR231GLFS"))
    )
    (comp (ref "SCL")
      (value "HOLE")
      (footprint "eagle-import:HOLE")
      (libsource (lib "eagle-import") (part "HOLE"))
    )
    (comp (ref "SDA")
      (value "HOLE")
      (footprint "eagle-import:HOLE")
      (libsource (lib "eagle-import") (part "HOLE"))
    )
    (comp (ref "SPI0_CS")
      (value "HOLE")
      (footprint "eagle-import:HOLE")
      (libsource (lib "eagle-import") (part "HOLE"))
    )
    (comp (ref "SPI0_MISO")
      (value "HOLE")
      (footprint "eagle-import:HOLE")
      (libsource (lib "eagle-import") (part "HOLE"))
    )
    (comp (ref "SPI0_MOSI")
      (value "HOLE")
      (footprint "eagle-import:HOLE")
      (libsource (lib "eagle-import") (part "HOLE"))
    )
    (comp (ref "SPI0_SCK")
      (value "HOLE")
      (footprint "eagle-import:HOLE")
      (libsource (lib "eagle-import") (part "HOLE"))
    )
    (comp (ref "SYS_RTC_1P8V")
      (value "TESTPAD/W_HOLE_1X1")
      (footprint "eagle-import:TESTPAD_W_HOLE_1X1")
      (libsource (lib "eagle-import") (part "TESTPAD/W_HOLE_1X1"))
    )
    (comp (ref "SYS_VDD1_3P3V")
      (value "TESTPAD/W_HOLE_1X1")
      (footprint "eagle-import:TESTPAD_W_HOLE_1X1")
      (libsource (lib "eagle-import") (part "TESTPAD/W_HOLE_1X1"))
    )
    (comp (ref "SYS_VDD2_3P3V")
      (value "TESTPAD/W_HOLE_1X1")
      (footprint "eagle-import:TESTPAD_W_HOLE_1X1")
      (libsource (lib "eagle-import") (part "TESTPAD/W_HOLE_1X1"))
    )
    (comp (ref "SYS_VDD_1P8V")
      (value "TESTPAD/W_HOLE_1X1")
      (footprint "eagle-import:TESTPAD_W_HOLE_1X1")
      (libsource (lib "eagle-import") (part "TESTPAD/W_HOLE_1X1"))
    )
    (comp (ref "SYS_VOUT")
      (value "TESTPAD/W_HOLE_1X1")
      (footprint "eagle-import:TESTPAD_W_HOLE_1X1")
      (libsource (lib "eagle-import") (part "TESTPAD/W_HOLE_1X1"))
    )
    (comp (ref "T_BAT")
      (value "TESTPAD/W_HOLE_1X1")
      (footprint "eagle-import:TESTPAD_W_HOLE_1X1")
      (libsource (lib "eagle-import") (part "TESTPAD/W_HOLE_1X1"))
    )
    (comp (ref "U$1")
      (value "HOLE")
      (footprint "eagle-import:HOLE")
      (libsource (lib "eagle-import") (part "HOLE"))
    )
    (comp (ref "U$2")
      (value "HOLE")
      (footprint "eagle-import:HOLE")
      (libsource (lib "eagle-import") (part "HOLE"))
    )
    (comp (ref "U$3")
      (value "HOLE")
      (footprint "eagle-import:HOLE")
      (libsource (lib "eagle-import") (part "HOLE"))
    )
    (comp (ref "U$4")
      (value "HOLE")
      (footprint "eagle-import:HOLE")
      (libsource (lib "eagle-import") (part "HOLE"))
    )
    (comp (ref "U$5")
      (value "HOLE")
      (footprint "eagle-import:HOLE")
      (libsource (lib "eagle-import") (part "HOLE"))
    )
    (comp (ref "U$6")
      (value "HOLE")
      (footprint "eagle-import:HOLE")
      (libsource (lib "eagle-import") (part "HOLE"))
    )
    (comp (ref "U$7")
      (value "HOLE")
      (footprint "eagle-import:HOLE")
      (libsource (lib "eagle-import") (part "HOLE"))
    )
    (comp (ref "U$8")
      (value "HOLE")
      (footprint "eagle-import:HOLE")
      (libsource (lib "eagle-import") (part "HOLE"))
    )
    (comp (ref "U$10")
      (value "HOLE")
      (footprint "eagle-import:HOLE")
      (libsource (lib "eagle-import") (part "HOLE"))
    )
    (comp (ref "U$11")
      (value "HOLE")
      (footprint "eagle-import:HOLE")
      (libsource (lib "eagle-import") (part "HOLE"))
    )
    (comp (ref "U$12")
      (value "HOLE")
      (footprint "eagle-import:HOLE")
      (libsource (lib "eagle-import") (part "HOLE"))
    )
    (comp (ref "U$13")
      (value "HOLE")
      (footprint "eagle-import:HOLE")
      (libsource (lib "eagle-import") (part "HOLE"))
    )
    (comp (ref "U1")
      (value "OSD3358-512M-BAS")
      (footprint "eagle-import:OSD335X-BGA-400")
      (libsource (lib "eagle-import") (part "OSD3358-512M-BAS"))
    )
    (comp (ref "U2")
      (value "TLVH431")
      (footprint "eagle-import:SOT23-3")
      (libsource (lib "eagle-import") (part "TLVH431"))
    )
    (comp (ref "U3")
      (value "SN74LVC1G07_DCK_5")
      (footprint "eagle-import:DCK5")
      (fields
        (field (name "GENERIC_PART_NUMBER") "SN74LVC1G07")
        (field (name "MANUFACTURER") "Texas Instruments")
        (field (name "MANUFACTURER_PART_NUMBER") "sn74lvc1g07_dck_5")
      )
      (libsource (lib "eagle-import") (part "SN74LVC1G07_DCK_5"))
    )
    (comp (ref "U4")
      (value "APX811SOT")
      (footprint "eagle-import:SOT143-R")
      (libsource (lib "eagle-import") (part "APX811SOT"))
    )
    (comp (ref "U5")
      (value "TPS2051")
      (footprint "eagle-import:S-PDSO-G08")
      (libsource (lib "eagle-import") (part "TPS2051"))
    )
    (comp (ref "U6")
      (value "TPD4S012_DRY_6")
      (footprint "eagle-import:DRY6")
      (fields
        (field (name "GENERIC_PART_NUMBER") "TPD4S012")
        (field (name "MANUFACTURER") "Texas Instruments")
        (field (name "MANUFACTURER_PART_NUMBER") "tpd4s012_dry_6")
      )
      (libsource (lib "eagle-import") (part "TPD4S012_DRY_6"))
    )
    (comp (ref "U7")
      (value "TPD4S012_DRY_6")
      (footprint "eagle-import:DRY6")
      (fields
        (field (name "GENERIC_PART_NUMBER") "TPD4S012")
        (field (name "MANUFACTURER") "Texas Instruments")
        (field (name "MANUFACTURER_PART_NUMBER") "tpd4s012_dry_6")
      )
      (libsource (lib "eagle-import") (part "TPD4S012_DRY_6"))
    )
    (comp (ref "U8")
      (value "24LC32A")
      (footprint "eagle-import:SOT23-5")
      (libsource (lib "eagle-import") (part "24LC32A"))
    )
    (comp (ref "UART0_RXD")
      (value "HOLE")
      (footprint "eagle-import:HOLE")
      (libsource (lib "eagle-import") (part "HOLE"))
    )
    (comp (ref "UART0_TXD")
      (value "HOLE")
      (footprint "eagle-import:HOLE")
      (libsource (lib "eagle-import") (part "HOLE"))
    )
    (comp (ref "USB_DC")
      (value "TESTPAD/W_HOLE_1X1")
      (footprint "eagle-import:TESTPAD_W_HOLE_1X1")
      (libsource (lib "eagle-import") (part "TESTPAD/W_HOLE_1X1"))
    )
    (comp (ref "VDDSHV_3P3V")
      (value "TESTPAD/W_HOLE_1X1")
      (footprint "eagle-import:TESTPAD_W_HOLE_1X1")
      (libsource (lib "eagle-import") (part "TESTPAD/W_HOLE_1X1"))
    )
    (comp (ref "VDDS_DDR")
      (value "TESTPAD/W_HOLE_1X1")
      (footprint "eagle-import:TESTPAD_W_HOLE_1X1")
      (libsource (lib "eagle-import") (part "TESTPAD/W_HOLE_1X1"))
    )
    (comp (ref "VDDS_PLL")
      (value "TESTPAD/W_HOLE_1X1")
      (footprint "eagle-import:TESTPAD_W_HOLE_1X1")
      (libsource (lib "eagle-import") (part "TESTPAD/W_HOLE_1X1"))
    )
    (comp (ref "VDD_5V")
      (value "TESTPAD/W_HOLE_1X1")
      (footprint "eagle-import:TESTPAD_W_HOLE_1X1")
      (libsource (lib "eagle-import") (part "TESTPAD/W_HOLE_1X1"))
    )
    (comp (ref "VDD_ADC")
      (value "TESTPAD/W_HOLE_1X1")
      (footprint "eagle-import:TESTPAD_W_HOLE_1X1")
      (libsource (lib "eagle-import") (part "TESTPAD/W_HOLE_1X1"))
    )
    (comp (ref "VDD_CORE")
      (value "TESTPAD/W_HOLE_1X1")
      (footprint "eagle-import:TESTPAD_W_HOLE_1X1")
      (libsource (lib "eagle-import") (part "TESTPAD/W_HOLE_1X1"))
    )
    (comp (ref "VDD_MPU")
      (value "TESTPAD/W_HOLE_1X1")
      (footprint "eagle-import:TESTPAD_W_HOLE_1X1")
      (libsource (lib "eagle-import") (part "TESTPAD/W_HOLE_1X1"))
    )
    (comp (ref "V_BAT")
      (value "TESTPAD/W_HOLE_1X1")
      (footprint "eagle-import:TESTPAD_W_HOLE_1X1")
      (libsource (lib "eagle-import") (part "TESTPAD/W_HOLE_1X1"))
    )
    (comp (ref "WP")
      (value "TESTPAD/W_HOLE_1X1")
      (footprint "eagle-import:TESTPAD_W_HOLE_1X1")
      (libsource (lib "eagle-import") (part "OSD3358_BAS_RefDesignParts_L2_TESTPAD/W_HOLE_1X1"))
    )
    (comp (ref "WRST")
      (value "TPTP15R")
      (footprint "eagle-import:TP15R")
      (libsource (lib "eagle-import") (part "TPTP15R"))
    )
    (comp (ref "X1")
      (value "PJ-102B_POWER_CON")
      (footprint "eagle-import:PJ-102B_POWER_CON")
      (libsource (lib "eagle-import") (part "PJ-102B_POWER_CON"))
    )
    (comp (ref "X2")
      (value "10118192-0001LF")
      (footprint "eagle-import:10118192-0001LF(MICRO-USB-B-AMPHENOL-FCI)")
      (libsource (lib "eagle-import") (part "10118192-0001LF"))
    )
    (comp (ref "X3")
      (value "USB_HOST_W/CHASSIS_GND")
      (footprint "eagle-import:USB_HOST_HORIZONTAL_W_CHASSIS_GND")
      (libsource (lib "eagle-import") (part "USB_HOST_W/CHASSIS_GND"))
    )
    (comp (ref "Y1")
      (value "7A-24.000MAAJ-T")
      (footprint "eagle-import:CRYSTAL-TXC-7A")
      (libsource (lib "eagle-import") (part "7A-24.000MAAJ-T"))
    )
    (comp (ref "Y2")
      (value "ABS07-32.768KHZ-T")
      (footprint "eagle-import:CRYSTAL_3.2X1.5")
      (libsource (lib "eagle-import") (part "ABS07-32.768KHZ-T"))
    )
  )
  (nets
    (net (code "1") (name "AGND") (class "Default")
      (node (ref "C1") (pin "1") (pinfunction "1_1") (pintype "passive"))
      (node (ref "C2") (pin "1") (pinfunction "1_1") (pintype "passive"))
      (node (ref "C3") (pin "1") (pinfunction "1_1") (pintype "passive"))
      (node (ref "U1") (pin "A6") (pinfunction "VSSA_ADC_A6") (pintype "bidirectional"))
      (node (ref "U1") (pin "A9") (pinfunction "VSSA_ADC_A9") (pintype "bidirectional"))
      (node (ref "U1") (pin "E8") (pinfunction "VSSA_ADC_E8") (pintype "bidirectional"))
    )
    (net (code "2") (name "CGND") (class "Default")
      (node (ref "MGT1") (pin "P$1") (pinfunction "P$1_P$1") (pintype "bidirectional"))
      (node (ref "MGT2") (pin "P$1") (pinfunction "P$1_P$1") (pintype "bidirectional"))
      (node (ref "MGT3") (pin "P$1") (pinfunction "P$1_P$1") (pintype "bidirectional"))
      (node (ref "MGT4") (pin "P$1") (pinfunction "P$1_P$1") (pintype "bidirectional"))
      (node (ref "R1") (pin "2") (pinfunction "2_2") (pintype "passive"))
      (node (ref "X2") (pin "CGND1") (pinfunction "SGND1_CGND1") (pintype "bidirectional"))
      (node (ref "X2") (pin "CGND2") (pinfunction "SGND2_CGND2") (pintype "bidirectional"))
      (node (ref "X2") (pin "CGND3") (pinfunction "SGND3_CGND3") (pintype "bidirectional"))
      (node (ref "X2") (pin "CGND4") (pinfunction "SGND4_CGND4") (pintype "bidirectional"))
      (node (ref "X2") (pin "CGND5") (pinfunction "SGND5_CGND5") (pintype "bidirectional"))
      (node (ref "X2") (pin "CGND6") (pinfunction "SGND6_CGND6") (pintype "bidirectional"))
      (node (ref "X3") (pin "5") (pinfunction "CG1_5") (pintype "bidirectional"))
      (node (ref "X3") (pin "6") (pinfunction "CG2_6") (pintype "bidirectional"))
    )
    (net (code "3") (name "EMMC_RSTN") (class "Default")
      (node (ref "IC1") (pin "K5") (pinfunction "RST#_K5") (pintype "bidirectional"))
      (node (ref "R44") (pin "1") (pinfunction "1_1") (pintype "passive"))
      (node (ref "U1") (pin "R14") (pinfunction "GPMC_A04_R14") (pintype "bidirectional"))
    )
    (net (code "4") (name "GND") (class "Default")
      (node (ref "C10") (pin "2") (pinfunction "2_2") (pintype "passive"))
      (node (ref "C11") (pin "-") (pinfunction "-_-") (pintype "passive"))
      (node (ref "C12") (pin "2") (pinfunction "2_2") (pintype "passive"))
      (node (ref "C13") (pin "2") (pinfunction "2_2") (pintype "passive"))
      (node (ref "C14") (pin "2") (pinfunction "2_2") (pintype "passive"))
      (node (ref "C15") (pin "2") (pinfunction "2_2") (pintype "passive"))
      (node (ref "C16") (pin "2") (pinfunction "2_2") (pintype "passive"))
      (node (ref "C17") (pin "2") (pinfunction "2_2") (pintype "passive"))
      (node (ref "C18") (pin "2") (pinfunction "2_2") (pintype "passive"))
      (node (ref "C19") (pin "2") (pinfunction "2_2") (pintype "passive"))
      (node (ref "C20") (pin "2") (pinfunction "2_2") (pintype "passive"))
      (node (ref "C21") (pin "2") (pinfunction "2_2") (pintype "passive"))
      (node (ref "C8") (pin "1") (pinfunction "1_1") (pintype "passive"))
      (node (ref "C9") (pin "1") (pinfunction "1_1") (pintype "passive"))
      (node (ref "D1") (pin "2") (pinfunction "C_2") (pintype "passive"))
      (node (ref "GND") (pin "P$1") (pinfunction "TP_P$1") (pintype "bidirectional"))
      (node (ref "GND.") (pin "P$1") (pinfunction "TP_P$1") (pintype "bidirectional"))
      (node (ref "GND3") (pin "P$1") (pinfunction "TP_P$1") (pintype "bidirectional"))
      (node (ref "IC1") (pin "C4") (pinfunction "VSSQ1_C4") (pintype "bidirectional"))
      (node (ref "IC1") (pin "E7") (pinfunction "VSS1_E7") (pintype "bidirectional"))
      (node (ref "IC1") (pin "G5") (pinfunction "VSS2_G5") (pintype "bidirectional"))
      (node (ref "IC1") (pin "H10") (pinfunction "VSS3_H10") (pintype "bidirectional"))
      (node (ref "IC1") (pin "K8") (pinfunction "VSS4_K8") (pintype "bidirectional"))
      (node (ref "IC1") (pin "N2") (pinfunction "VSSQ2_N2") (pintype "bidirectional"))
      (node (ref "IC1") (pin "N5") (pinfunction "VSSQ3_N5") (pintype "bidirectional"))
      (node (ref "IC1") (pin "P4") (pinfunction "VSSQ4_P4") (pintype "bidirectional"))
      (node (ref "IC1") (pin "P6") (pinfunction "VSSQ5_P6") (pintype "bidirectional"))
      (node (ref "J1") (pin "10") (pinfunction "CARD_DET2_10") (pintype "passive"))
      (node (ref "J1") (pin "6") (pinfunction "VSS_6") (pintype "power_in"))
      (node (ref "J1") (pin "G1") (pinfunction "GND_G1") (pintype "power_in"))
      (node (ref "J1") (pin "G2") (pinfunction "GND_G2") (pintype "power_in"))
      (node (ref "J1") (pin "G3") (pinfunction "GND_G3") (pintype "power_in"))
      (node (ref "J1") (pin "G4") (pinfunction "GND_G4") (pintype "power_in"))
      (node (ref "JTAG") (pin "10") (pinfunction "GND2_10") (pintype "bidirectional"))
      (node (ref "JTAG") (pin "12") (pinfunction "GND3_12") (pintype "bidirectional"))
      (node (ref "JTAG") (pin "16") (pinfunction "GND4_16") (pintype "bidirectional"))
      (node (ref "JTAG") (pin "20") (pinfunction "GND5_20") (pintype "bidirectional"))
      (node (ref "JTAG") (pin "4") (pinfunction "TDIS_4") (pintype "bidirectional"))
      (node (ref "JTAG") (pin "8") (pinfunction "GND1_8") (pintype "bidirectional"))
      (node (ref "R1") (pin "1") (pinfunction "1_1") (pintype "passive"))
      (node (ref "R10") (pin "1") (pinfunction "1_1") (pintype "passive"))
      (node (ref "R13") (pin "2") (pinfunction "2_2") (pintype "passive"))
      (node (ref "R15") (pin "1") (pinfunction "1_1") (pintype "passive"))
      (node (ref "R17") (pin "1") (pinfunction "1_1") (pintype "passive"))
      (node (ref "R18") (pin "1") (pinfunction "1_1") (pintype "passive"))
      (node (ref "R19") (pin "1") (pinfunction "1_1") (pintype "passive"))
      (node (ref "R22") (pin "1") (pinfunction "1_1") (pintype "passive"))
      (node (ref "R23") (pin "1") (pinfunction "1_1") (pintype "passive"))
      (node (ref "R24") (pin "1") (pinfunction "1_1") (pintype "passive"))
      (node (ref "R25") (pin "1") (pinfunction "1_1") (pintype "passive"))
      (node (ref "R26") (pin "1") (pinfunction "1_1") (pintype "passive"))
      (node (ref "R27") (pin "1") (pinfunction "1_1") (pintype "passive"))
      (node (ref "R28") (pin "1") (pinfunction "1_1") (pintype "passive"))
      (node (ref "R29") (pin "1") (pinfunction "1_1") (pintype "passive"))
      (node (ref "R30") (pin "1") (pinfunction "1_1") (pintype "passive"))
      (node (ref "R32") (pin "1") (pinfunction "1_1") (pintype "passive"))
      (node (ref "R33") (pin "1") (pinfunction "1_1") (pintype "passive"))
      (node (ref "R34") (pin "1") (pinfunction "1_1") (pintype "passive"))
      (node (ref "R57") (pin "1") (pinfunction "1_1") (pintype "passive"))
      (node (ref "R58") (pin "1") (pinfunction "1_1") (pintype "passive"))
      (node (ref "R59") (pin "1") (pinfunction "1_1") (pintype "passive"))
      (node (ref "R60") (pin "1") (pinfunction "1_1") (pintype "passive"))
      (node (ref "S1") (pin "1") (pinfunction "1_1") (pintype "bidirectional"))
      (node (ref "S1") (pin "3") (pinfunction "3_3") (pintype "bidirectional"))
      (node (ref "S2") (pin "2") (pinfunction "2_2") (pintype "bidirectional"))
      (node (ref "S2") (pin "4") (pinfunction "4_4") (pintype "bidirectional"))
      (node (ref "S3") (pin "2") (pinfunction "2_2") (pintype "bidirectional"))
      (node (ref "S3") (pin "4") (pinfunction "4_4") (pintype "bidirectional"))
      (node (ref "S4") (pin "2") (pinfunction "2_2") (pintype "bidirectional"))
      (node (ref "S4") (pin "4") (pinfunction "4_4") (pintype "bidirectional"))
      (node (ref "U1") (pin "A1") (pinfunction "VSS_A1") (pintype "bidirectional"))
      (node (ref "U1") (pin "A18") (pinfunction "VSS_A18") (pintype "bidirectional"))
      (node (ref "U1") (pin "E19") (pinfunction "VSS_E19") (pintype "bidirectional"))
      (node (ref "U1") (pin "E20") (pinfunction "VSS_E20") (pintype "bidirectional"))
      (node (ref "U1") (pin "F19") (pinfunction "VSS_F19") (pintype "bidirectional"))
      (node (ref "U1") (pin "F8") (pinfunction "VSS_F8") (pintype "bidirectional"))
      (node (ref "U1") (pin "G11") (pinfunction "VSS_G11") (pintype "bidirectional"))
      (node (ref "U1") (pin "G12") (pinfunction "VSS_G12") (pintype "bidirectional"))
      (node (ref "U1") (pin "G19") (pinfunction "VSS_G19") (pintype "bidirectional"))
      (node (ref "U1") (pin "G8") (pinfunction "VSS_G8") (pintype "bidirectional"))
      (node (ref "U1") (pin "G9") (pinfunction "VSS_G9") (pintype "bidirectional"))
      (node (ref "U1") (pin "H10") (pinfunction "VSS_H10") (pintype "bidirectional"))
      (node (ref "U1") (pin "H12") (pinfunction "VSS_H12") (pintype "bidirectional"))
      (node (ref "U1") (pin "H19") (pinfunction "VSS_H19") (pintype "bidirectional"))
      (node (ref "U1") (pin "H6") (pinfunction "VSS_H6") (pintype "bidirectional"))
      (node (ref "U1") (pin "H7") (pinfunction "VSS_H7") (pintype "bidirectional"))
      (node (ref "U1") (pin "H8") (pinfunction "VSS_H8") (pintype "bidirectional"))
      (node (ref "U1") (pin "H9") (pinfunction "VSS_H9") (pintype "bidirectional"))
      (node (ref "U1") (pin "J10") (pinfunction "VSS_J10") (pintype "bidirectional"))
      (node (ref "U1") (pin "J11") (pinfunction "VSS_J11") (pintype "bidirectional"))
      (node (ref "U1") (pin "J19") (pinfunction "VSS_J19") (pintype "bidirectional"))
      (node (ref "U1") (pin "J20") (pinfunction "VSS_J20") (pintype "bidirectional"))
      (node (ref "U1") (pin "J6") (pinfunction "VSS_J6") (pintype "bidirectional"))
      (node (ref "U1") (pin "J7") (pinfunction "VSS_J7") (pintype "bidirectional"))
      (node (ref "U1") (pin "J8") (pinfunction "VSS_J8") (pintype "bidirectional"))
      (node (ref "U1") (pin "J9") (pinfunction "VSS_J9") (pintype "bidirectional"))
      (node (ref "U1") (pin "K10") (pinfunction "VSS_K10") (pintype "bidirectional"))
      (node (ref "U1") (pin "K11") (pinfunction "VSS_K11") (pintype "bidirectional"))
      (node (ref "U1") (pin "K19") (pinfunction "VSS_K19") (pintype "bidirectional"))
      (node (ref "U1") (pin "K7") (pinfunction "VSS_K7") (pintype "bidirectional"))
      (node (ref "U1") (pin "K9") (pinfunction "VSS_K9") (pintype "bidirectional"))
      (node (ref "U1") (pin "L10") (pinfunction "VSS_L10") (pintype "bidirectional"))
      (node (ref "U1") (pin "L11") (pinfunction "VSS_L11") (pintype "bidirectional"))
      (node (ref "U1") (pin "L12") (pinfunction "VSS_L12") (pintype "bidirectional"))
      (node (ref "U1") (pin "L13") (pinfunction "VSS_L13") (pintype "bidirectional"))
      (node (ref "U1") (pin "L19") (pinfunction "VSS_L19") (pintype "bidirectional"))
      (node (ref "U1") (pin "M10") (pinfunction "VSS_M10") (pintype "bidirectional"))
      (node (ref "U1") (pin "M12") (pinfunction "VSS_M12") (pintype "bidirectional"))
      (node (ref "U1") (pin "M14") (pinfunction "VSS_M14") (pintype "bidirectional"))
      (node (ref "U1") (pin "M19") (pinfunction "VSS_M19") (pintype "bidirectional"))
      (node (ref "U1") (pin "M6") (pinfunction "VSS_M6") (pintype "bidirectional"))
      (node (ref "U1") (pin "M7") (pinfunction "VSS_M7") (pintype "bidirectional"))
      (node (ref "U1") (pin "M8") (pinfunction "VSS_M8") (pintype "bidirectional"))
      (node (ref "U1") (pin "M9") (pinfunction "VSS_M9") (pintype "bidirectional"))
      (node (ref "U1") (pin "N10") (pinfunction "VSS_N10") (pintype "bidirectional"))
      (node (ref "U1") (pin "N11") (pinfunction "VSS_N11") (pintype "bidirectional"))
      (node (ref "U1") (pin "N14") (pinfunction "VSS_N14") (pintype "bidirectional"))
      (node (ref "U1") (pin "N19") (pinfunction "VSS_N19") (pintype "bidirectional"))
      (node (ref "U1") (pin "N20") (pinfunction "VSS_N20") (pintype "bidirectional"))
      (node (ref "U1") (pin "N7") (pinfunction "VSS_N7") (pintype "bidirectional"))
      (node (ref "U1") (pin "P17") (pinfunction "USB1_ID_P17") (pintype "bidirectional"))
      (node (ref "U1") (pin "P19") (pinfunction "VSS_P19") (pintype "bidirectional"))
      (node (ref "U1") (pin "P20") (pinfunction "VSS_P20") (pintype "bidirectional"))
      (node (ref "U1") (pin "R19") (pinfunction "VSS_R19") (pintype "bidirectional"))
      (node (ref "U1") (pin "R20") (pinfunction "VSS_R20") (pintype "bidirectional"))
      (node (ref "U1") (pin "T19") (pinfunction "VSS_T19") (pintype "bidirectional"))
      (node (ref "U1") (pin "T20") (pinfunction "VSS_T20") (pintype "bidirectional"))
      (node (ref "U1") (pin "U19") (pinfunction "VSS_U19") (pintype "bidirectional"))
      (node (ref "U1") (pin "V1") (pinfunction "VSS_V1") (pintype "bidirectional"))
      (node (ref "U1") (pin "V18") (pinfunction "VSS_V18") (pintype "bidirectional"))
      (node (ref "U1") (pin "V19") (pinfunction "VSS_V19") (pintype "bidirectional"))
      (node (ref "U1") (pin "W10") (pinfunction "VSS_W10") (pintype "bidirectional"))
      (node (ref "U1") (pin "W11") (pinfunction "VSS_W11") (pintype "bidirectional"))
      (node (ref "U1") (pin "W12") (pinfunction "VSS_W12") (pintype "bidirectional"))
      (node (ref "U1") (pin "W13") (pinfunction "VSS_W13") (pintype "bidirectional"))
      (node (ref "U1") (pin "W14") (pinfunction "VSS_W14") (pintype "bidirectional"))
      (node (ref "U1") (pin "W15") (pinfunction "VSS_W15") (pintype "bidirectional"))
      (node (ref "U1") (pin "W16") (pinfunction "VSS_W16") (pintype "bidirectional"))
      (node (ref "U1") (pin "W17") (pinfunction "VSS_W17") (pintype "bidirectional"))
      (node (ref "U1") (pin "W18") (pinfunction "VSS_W18") (pintype "bidirectional"))
      (node (ref "U1") (pin "W19") (pinfunction "VSS_W19") (pintype "bidirectional"))
      (node (ref "U1") (pin "W2") (pinfunction "VSS_W2") (pintype "bidirectional"))
      (node (ref "U1") (pin "W20") (pinfunction "VSS_W20") (pintype "bidirectional"))
      (node (ref "U1") (pin "W3") (pinfunction "VSS_W3") (pintype "bidirectional"))
      (node (ref "U1") (pin "W5") (pinfunction "VSS_W5") (pintype "bidirectional"))
      (node (ref "U1") (pin "W6") (pinfunction "VSS_W6") (pintype "bidirectional"))
      (node (ref "U1") (pin "W7") (pinfunction "VSS_W7") (pintype "bidirectional"))
      (node (ref "U1") (pin "W8") (pinfunction "VSS_W8") (pintype "bidirectional"))
      (node (ref "U1") (pin "W9") (pinfunction "VSS_W9") (pintype "bidirectional"))
      (node (ref "U1") (pin "Y10") (pinfunction "VSS_Y10") (pintype "bidirectional"))
      (node (ref "U1") (pin "Y12") (pinfunction "VSS_Y12") (pintype "bidirectional"))
      (node (ref "U1") (pin "Y15") (pinfunction "VSS_Y15") (pintype "bidirectional"))
      (node (ref "U1") (pin "Y18") (pinfunction "VSS_Y18") (pintype "bidirectional"))
      (node (ref "U1") (pin "Y7") (pinfunction "VSS_Y7") (pintype "bidirectional"))
      (node (ref "U3") (pin "3") (pinfunction "GND_3") (pintype "power_in"))
      (node (ref "U4") (pin "1") (pinfunction "GND_1") (pintype "bidirectional"))
      (node (ref "U5") (pin "1") (pinfunction "GND_1") (pintype "power_in"))
      (node (ref "U5") (pin "TH") (pinfunction "PAD_TH") (pintype "power_in"))
      (node (ref "U6") (pin "4") (pinfunction "GND_4") (pintype "power_in"))
      (node (ref "U7") (pin "4") (pinfunction "GND_4") (pintype "power_in"))
      (node (ref "U8") (pin "2") (pinfunction "VSS_2") (pintype "bidirectional"))
      (node (ref "X1") (pin "OUT") (pinfunction "OUT_OUT") (pintype "bidirectional"))
      (node (ref "X2") (pin "GND") (pinfunction "GND_GND") (pintype "input"))
      (node (ref "X3") (pin "4") (pinfunction "GND_4") (pintype "bidirectional"))
    )
    (net (code "5") (name "I2C0_SCL") (class "Default")
      (node (ref "R4") (pin "1") (pinfunction "1_1") (pintype "passive"))
      (node (ref "SDA") (pin "P$1") (pinfunction "P$1_P$1") (pintype "bidirectional"))
      (node (ref "U1") (pin "C16") (pinfunction "I2C0_SCL_C16") (pintype "bidirectional"))
      (node (ref "U1") (pin "C20") (pinfunction "PMIC_IN_I2C_SCL_C20") (pintype "bidirectional"))
      (node (ref "U8") (pin "1") (pinfunction "SCL_1") (pintype "bidirectional"))
    )
    (net (code "6") (name "I2C0_SDA") (class "Default")
      (node (ref "R3") (pin "1") (pinfunction "1_1") (pintype "passive"))
      (node (ref "SCL") (pin "P$1") (pinfunction "P$1_P$1") (pintype "bidirectional"))
      (node (ref "U1") (pin "C17") (pinfunction "I2C0_SDA_C17") (pintype "bidirectional"))
      (node (ref "U1") (pin "C19") (pinfunction "PMIC_IN_I2C_SDA_C19") (pintype "bidirectional"))
      (node (ref "U8") (pin "3") (pinfunction "SDA_3") (pintype "bidirectional"))
    )
    (net (code "7") (name "JTAG_EMU0") (class "Default")
      (node (ref "JTAG") (pin "13") (pinfunction "EMU0_13") (pintype "bidirectional"))
      (node (ref "R14") (pin "1") (pinfunction "1_1") (pintype "passive"))
      (node (ref "U1") (pin "C14") (pinfunction "EMU0_C14") (pintype "bidirectional"))
    )
    (net (code "8") (name "JTAG_EMU1") (class "Default")
      (node (ref "JTAG") (pin "14") (pinfunction "EMU1_14") (pintype "bidirectional"))
      (node (ref "R16") (pin "1") (pinfunction "1_1") (pintype "passive"))
      (node (ref "U1") (pin "B14") (pinfunction "EMU1_B14") (pintype "bidirectional"))
    )
    (net (code "9") (name "JTAG_EMU2") (class "Default")
      (node (ref "JTAG") (pin "17") (pinfunction "EMU2_17") (pintype "bidirectional"))
      (node (ref "U1") (pin "A15") (pinfunction "XDMA_EVENT_INTR0_A15") (pintype "bidirectional"))
    )
    (net (code "10") (name "JTAG_EMU3") (class "Default")
      (node (ref "JTAG") (pin "18") (pinfunction "EMU3_18") (pintype "bidirectional"))
      (node (ref "U1") (pin "D14") (pinfunction "XDMA_EVENT_INTR1_D14") (pintype "bidirectional"))
    )
    (net (code "11") (name "JTAG_TCK") (class "Default")
      (node (ref "JTAG") (pin "11") (pinfunction "TCK_11") (pintype "bidirectional"))
      (node (ref "JTAG") (pin "9") (pinfunction "TCKRTN_9") (pintype "bidirectional"))
      (node (ref "U1") (pin "A12") (pinfunction "TCK_A12") (pintype "bidirectional"))
    )
    (net (code "12") (name "JTAG_TDI") (class "Default")
      (node (ref "JTAG") (pin "3") (pinfunction "TDI_3") (pintype "bidirectional"))
      (node (ref "U1") (pin "B11") (pinfunction "TDI_B11") (pintype "bidirectional"))
    )
    (net (code "13") (name "JTAG_TDO") (class "Default")
      (node (ref "JTAG") (pin "7") (pinfunction "TDO_7") (pintype "bidirectional"))
      (node (ref "U1") (pin "A11") (pinfunction "TDO_A11") (pintype "bidirectional"))
    )
    (net (code "14") (name "JTAG_TMS") (class "Default")
      (node (ref "JTAG") (pin "1") (pinfunction "TMS_1") (pintype "bidirectional"))
      (node (ref "U1") (pin "C11") (pinfunction "TMS_C11") (pintype "bidirectional"))
    )
    (net (code "15") (name "JTAG_TRSTN") (class "Default")
      (node (ref "JTAG") (pin "2") (pinfunction "TRSTN_2") (pintype "bidirectional"))
      (node (ref "R15") (pin "2") (pinfunction "2_2") (pintype "passive"))
      (node (ref "U1") (pin "B10") (pinfunction "TRSTN_B10") (pintype "bidirectional"))
    )
    (net (code "16") (name "LCD_DATA0") (class "Default")
      (node (ref "R17") (pin "2") (pinfunction "2_2") (pintype "passive"))
      (node (ref "U1") (pin "R1") (pinfunction "LCD_DATA00_R1") (pintype "bidirectional"))
    )
    (net (code "17") (name "LCD_DATA1") (class "Default")
      (node (ref "R18") (pin "2") (pinfunction "2_2") (pintype "passive"))
      (node (ref "U1") (pin "R2") (pinfunction "LCD_DATA01_R2") (pintype "bidirectional"))
    )
    (net (code "18") (name "LCD_DATA2") (class "Default")
      (node (ref "R19") (pin "2") (pinfunction "2_2") (pintype "passive"))
      (node (ref "U1") (pin "R3") (pinfunction "LCD_DATA02_R3") (pintype "bidirectional"))
    )
    (net (code "19") (name "LCD_DATA3") (class "Default")
      (node (ref "R20") (pin "1") (pinfunction "1_1") (pintype "passive"))
      (node (ref "U1") (pin "R4") (pinfunction "LCD_DATA03_R4") (pintype "bidirectional"))
    )
    (net (code "20") (name "LCD_DATA4") (class "Default")
      (node (ref "R21") (pin "1") (pinfunction "1_1") (pintype "passive"))
      (node (ref "U1") (pin "T1") (pinfunction "LCD_DATA04_T1") (pintype "bidirectional"))
    )
    (net (code "21") (name "LCD_DATA5") (class "Default")
      (node (ref "R22") (pin "2") (pinfunction "2_2") (pintype "passive"))
      (node (ref "U1") (pin "T2") (pinfunction "LCD_DATA05_T2") (pintype "bidirectional"))
    )
    (net (code "22") (name "LCD_DATA6") (class "Default")
      (node (ref "R23") (pin "2") (pinfunction "2_2") (pintype "passive"))
      (node (ref "U1") (pin "T3") (pinfunction "LCD_DATA06_T3") (pintype "bidirectional"))
    )
    (net (code "23") (name "LCD_DATA7") (class "Default")
      (node (ref "R24") (pin "2") (pinfunction "2_2") (pintype "passive"))
      (node (ref "U1") (pin "T4") (pinfunction "LCD_DATA07_T4") (pintype "bidirectional"))
    )
    (net (code "24") (name "LCD_DATA8") (class "Default")
      (node (ref "R25") (pin "2") (pinfunction "2_2") (pintype "passive"))
      (node (ref "U1") (pin "U1") (pinfunction "LCD_DATA08_U1") (pintype "bidirectional"))
    )
    (net (code "25") (name "LCD_DATA9") (class "Default")
      (node (ref "R26") (pin "2") (pinfunction "2_2") (pintype "passive"))
      (node (ref "U1") (pin "U2") (pinfunction "LCD_DATA09_U2") (pintype "bidirectional"))
    )
    (net (code "26") (name "LCD_DATA10") (class "Default")
      (node (ref "R27") (pin "2") (pinfunction "2_2") (pintype "passive"))
      (node (ref "U1") (pin "U3") (pinfunction "LCD_DATA10_U3") (pintype "bidirectional"))
    )
    (net (code "27") (name "LCD_DATA11") (class "Default")
      (node (ref "R28") (pin "2") (pinfunction "2_2") (pintype "passive"))
      (node (ref "U1") (pin "U4") (pinfunction "LCD_DATA11_U4") (pintype "bidirectional"))
    )
    (net (code "28") (name "LCD_DATA12") (class "Default")
      (node (ref "R29") (pin "2") (pinfunction "2_2") (pintype "passive"))
      (node (ref "U$2") (pin "P$1") (pinfunction "P$1_P$1") (pintype "bidirectional"))
      (node (ref "U1") (pin "V2") (pinfunction "LCD_DATA12_V2") (pintype "bidirectional"))
    )
    (net (code "29") (name "LCD_DATA13") (class "Default")
      (node (ref "R30") (pin "2") (pinfunction "2_2") (pintype "passive"))
      (node (ref "U$3") (pin "P$1") (pinfunction "P$1_P$1") (pintype "bidirectional"))
      (node (ref "U1") (pin "V3") (pinfunction "LCD_DATA13_V3") (pintype "bidirectional"))
    )
    (net (code "30") (name "LCD_DATA14") (class "Default")
      (node (ref "R31") (pin "1") (pinfunction "1_1") (pintype "passive"))
      (node (ref "U1") (pin "V4") (pinfunction "LCD_DATA14_V4") (pintype "bidirectional"))
    )
    (net (code "31") (name "LCD_DATA15") (class "Default")
      (node (ref "R32") (pin "2") (pinfunction "2_2") (pintype "passive"))
      (node (ref "U1") (pin "T5") (pinfunction "LCD_DATA15_T5") (pintype "bidirectional"))
    )
    (net (code "32") (name "MMC0_CD") (class "Default")
      (node (ref "J1") (pin "9") (pinfunction "CARD_DET1_9") (pintype "passive"))
      (node (ref "JTAG") (pin "19") (pinfunction "EMU4_19") (pintype "bidirectional"))
      (node (ref "R43") (pin "1") (pinfunction "1_1") (pintype "passive"))
    )
    (net (code "33") (name "MMC0_CLKO") (class "Default")
      (node (ref "J1") (pin "5") (pinfunction "CLK_5") (pintype "input"))
      (node (ref "R40") (pin "1") (pinfunction "1_1") (pintype "passive"))
      (node (ref "U1") (pin "G17") (pinfunction "MMC0_CLK_G17") (pintype "bidirectional"))
    )
    (net (code "34") (name "MMC0_CMD") (class "Default")
      (node (ref "J1") (pin "3") (pinfunction "CMD_3") (pintype "input"))
      (node (ref "R39") (pin "1") (pinfunction "1_1") (pintype "passive"))
      (node (ref "U1") (pin "C15") (pinfunction "SPI0_CS1_C15") (pintype "bidirectional"))
      (node (ref "U1") (pin "G18") (pinfunction "MMC0_CMD_G18") (pintype "bidirectional"))
    )
    (net (code "35") (name "MMC0_DAT0") (class "Default")
      (node (ref "J1") (pin "7") (pinfunction "DAT0_7") (pintype "bidirectional"))
      (node (ref "R37") (pin "1") (pinfunction "1_1") (pintype "passive"))
      (node (ref "U1") (pin "G16") (pinfunction "MMC0_DAT0_G16") (pintype "bidirectional"))
    )
    (net (code "36") (name "MMC0_DAT1") (class "Default")
      (node (ref "J1") (pin "8") (pinfunction "DAT1_8") (pintype "bidirectional"))
      (node (ref "R38") (pin "1") (pinfunction "1_1") (pintype "passive"))
      (node (ref "U1") (pin "G15") (pinfunction "MMC0_DAT1_G15") (pintype "bidirectional"))
    )
    (net (code "37") (name "MMC0_DAT2") (class "Default")
      (node (ref "J1") (pin "1") (pinfunction "DAT2_1") (pintype "bidirectional"))
      (node (ref "R41") (pin "1") (pinfunction "1_1") (pintype "passive"))
      (node (ref "U1") (pin "F18") (pinfunction "MMC0_DAT2_F18") (pintype "bidirectional"))
    )
    (net (code "38") (name "MMC0_DAT3") (class "Default")
      (node (ref "J1") (pin "2") (pinfunction "CD/DAT3_2") (pintype "bidirectional"))
      (node (ref "R42") (pin "1") (pinfunction "1_1") (pintype "passive"))
      (node (ref "U1") (pin "F17") (pinfunction "MMC0_DAT3_F17") (pintype "bidirectional"))
    )
    (net (code "39") (name "MMC1_CLK") (class "Default")
      (node (ref "IC1") (pin "M6") (pinfunction "CLK_M6") (pintype "bidirectional"))
      (node (ref "R45") (pin "1") (pinfunction "1_1") (pintype "passive"))
      (node (ref "R55") (pin "2") (pinfunction "2_2") (pintype "passive"))
    )
    (net (code "40") (name "MMC1_CMD") (class "Default")
      (node (ref "IC1") (pin "M5") (pinfunction "CMD_M5") (pintype "bidirectional"))
      (node (ref "R46") (pin "1") (pinfunction "1_1") (pintype "passive"))
      (node (ref "U1") (pin "V9") (pinfunction "GPMC_CSN2_V9") (pintype "bidirectional"))
    )
    (net (code "41") (name "MMC1_DAT0") (class "Default")
      (node (ref "IC1") (pin "A3") (pinfunction "DAT0_A3") (pintype "bidirectional"))
      (node (ref "R54") (pin "1") (pinfunction "1_1") (pintype "passive"))
      (node (ref "U1") (pin "U7") (pinfunction "GPMC_AD00_U7") (pintype "bidirectional"))
    )
    (net (code "42") (name "MMC1_DAT1") (class "Default")
      (node (ref "IC1") (pin "A4") (pinfunction "DAT1_A4") (pintype "bidirectional"))
      (node (ref "R53") (pin "1") (pinfunction "1_1") (pintype "passive"))
      (node (ref "U1") (pin "V7") (pinfunction "GPMC_AD01_V7") (pintype "bidirectional"))
    )
    (net (code "43") (name "MMC1_DAT2") (class "Default")
      (node (ref "IC1") (pin "A5") (pinfunction "DAT2_A5") (pintype "bidirectional"))
      (node (ref "R52") (pin "1") (pinfunction "1_1") (pintype "passive"))
      (node (ref "U1") (pin "R8") (pinfunction "GPMC_AD02_R8") (pintype "bidirectional"))
    )
    (net (code "44") (name "MMC1_DAT3") (class "Default")
      (node (ref "IC1") (pin "B2") (pinfunction "DAT3_B2") (pintype "bidirectional"))
      (node (ref "R51") (pin "1") (pinfunction "1_1") (pintype "passive"))
      (node (ref "U1") (pin "T8") (pinfunction "GPMC_AD03_T8") (pintype "bidirectional"))
    )
    (net (code "45") (name "MMC1_DAT4") (class "Default")
      (node (ref "IC1") (pin "B3") (pinfunction "DAT4_B3") (pintype "bidirectional"))
      (node (ref "R50") (pin "1") (pinfunction "1_1") (pintype "passive"))
      (node (ref "U1") (pin "U8") (pinfunction "GPMC_AD04_U8") (pintype "bidirectional"))
    )
    (net (code "46") (name "MMC1_DAT5") (class "Default")
      (node (ref "IC1") (pin "B4") (pinfunction "DAT5_B4") (pintype "bidirectional"))
      (node (ref "R49") (pin "1") (pinfunction "1_1") (pintype "passive"))
      (node (ref "U1") (pin "V8") (pinfunction "GPMC_AD05_V8") (pintype "bidirectional"))
    )
    (net (code "47") (name "MMC1_DAT6") (class "Default")
      (node (ref "IC1") (pin "B5") (pinfunction "DAT6_B5") (pintype "bidirectional"))
      (node (ref "R48") (pin "1") (pinfunction "1_1") (pintype "passive"))
      (node (ref "U1") (pin "R9") (pinfunction "GPMC_AD06_R9") (pintype "bidirectional"))
    )
    (net (code "48") (name "MMC1_DAT7") (class "Default")
      (node (ref "IC1") (pin "B6") (pinfunction "DAT7_B6") (pintype "bidirectional"))
      (node (ref "R47") (pin "1") (pinfunction "1_1") (pintype "passive"))
      (node (ref "U1") (pin "T9") (pinfunction "GPMC_AD07_T9") (pintype "bidirectional"))
    )
    (net (code "49") (name "Net-(5V_BAT-TP)") (class "Default")
      (node (ref "5V_BAT") (pin "P$1") (pinfunction "TP_P$1") (pintype "bidirectional"))
      (node (ref "U1") (pin "Y2") (pinfunction "VIN_BAT_Y2") (pintype "bidirectional"))
      (node (ref "U1") (pin "Y3") (pinfunction "VIN_BAT_Y3") (pintype "bidirectional"))
    )
    (net (code "50") (name "Net-(D1-A)") (class "Default")
      (node (ref "D1") (pin "1") (pinfunction "A_1") (pintype "passive"))
      (node (ref "R5") (pin "1") (pinfunction "1_1") (pintype "passive"))
    )
    (net (code "51") (name "Net-(D2-A)") (class "Default")
      (node (ref "D2") (pin "1") (pinfunction "A_1") (pintype "passive"))
      (node (ref "U1") (pin "U14") (pinfunction "GPMC_A02_U14") (pintype "bidirectional"))
    )
    (net (code "52") (name "Net-(D2-C)") (class "Default")
      (node (ref "D2") (pin "2") (pinfunction "C_2") (pintype "passive"))
      (node (ref "R33") (pin "2") (pinfunction "2_2") (pintype "passive"))
    )
    (net (code "53") (name "Net-(D3-C)") (class "Default")
      (node (ref "D3") (pin "2") (pinfunction "C_2") (pintype "passive"))
      (node (ref "R57") (pin "2") (pinfunction "2_2") (pintype "passive"))
    )
    (net (code "54") (name "Net-(D4-C)") (class "Default")
      (node (ref "D4") (pin "2") (pinfunction "C_2") (pintype "passive"))
      (node (ref "R58") (pin "2") (pinfunction "2_2") (pintype "passive"))
    )
    (net (code "55") (name "Net-(D5-C)") (class "Default")
      (node (ref "D5") (pin "2") (pinfunction "C_2") (pintype "passive"))
      (node (ref "R59") (pin "2") (pinfunction "2_2") (pintype "passive"))
    )
    (net (code "56") (name "Net-(D6-C)") (class "Default")
      (node (ref "D6") (pin "2") (pinfunction "C_2") (pintype "passive"))
      (node (ref "R60") (pin "2") (pinfunction "2_2") (pintype "passive"))
    )
    (net (code "57") (name "Net-(IC1-VDDI)") (class "Default")
      (node (ref "C20") (pin "1") (pinfunction "1_1") (pintype "passive"))
      (node (ref "IC1") (pin "C2") (pinfunction "VDDI_C2") (pintype "bidirectional"))
    )
    (net (code "58") (name "Net-(R36-Pad2)") (class "Default")
      (node (ref "R36") (pin "2") (pinfunction "2_2") (pintype "passive"))
      (node (ref "X2") (pin "VBUS") (pinfunction "VBUS_VBUS") (pintype "input"))
    )
    (net (code "59") (name "Net-(SYS_RTC_1P8V-TP)") (class "Default")
      (node (ref "SYS_RTC_1P8V") (pin "P$1") (pinfunction "TP_P$1") (pintype "bidirectional"))
      (node (ref "U1") (pin "D7") (pinfunction "SYS_RTC_1P8V_D7") (pintype "bidirectional"))
    )
    (net (code "60") (name "Net-(SYS_VDD_1P8V-TP)") (class "Default")
      (node (ref "SYS_VDD_1P8V") (pin "P$1") (pinfunction "TP_P$1") (pintype "bidirectional"))
      (node (ref "U1") (pin "E9") (pinfunction "SYS_VDD_1P8V_E9") (pintype "bidirectional"))
    )
    (net (code "61") (name "Net-(T_BAT-TP)") (class "Default")
      (node (ref "T_BAT") (pin "P$1") (pinfunction "TP_P$1") (pintype "bidirectional"))
      (node (ref "U1") (pin "W1") (pinfunction "BAT_TEMP_W1") (pintype "bidirectional"))
    )
    (net (code "62") (name "Net-(U1A-BAT_VOLT)") (class "Default")
      (node (ref "U1") (pin "Y1") (pinfunction "BAT_VOLT_Y1") (pintype "bidirectional"))
      (node (ref "V_BAT") (pin "P$1") (pinfunction "TP_P$1") (pintype "bidirectional"))
    )
    (net (code "63") (name "Net-(U1A-EXTINTN)") (class "Default")
      (node (ref "NINT") (pin "TP") (pinfunction "TP_TP") (pintype "input"))
      (node (ref "U1") (pin "B18") (pinfunction "EXTINTN_B18") (pintype "bidirectional"))
      (node (ref "U1") (pin "B19") (pinfunction "PMIC_OUT_NINT_B19") (pintype "output"))
    )
    (net (code "64") (name "Net-(U1A-EXT_WAKEUP)") (class "Default")
      (node (ref "NWKP") (pin "TP") (pinfunction "TP_TP") (pintype "input"))
      (node (ref "U1") (pin "A19") (pinfunction "PMIC_OUT_NWAKEUP_A19") (pintype "output"))
      (node (ref "U1") (pin "C5") (pinfunction "EXT_WAKEUP_C5") (pintype "bidirectional"))
    )
    (net (code "65") (name "Net-(U1A-PMIC_IN_PB_IN)") (class "Default")
      (node (ref "S1") (pin "2") (pinfunction "2_2") (pintype "bidirectional"))
      (node (ref "S1") (pin "4") (pinfunction "4_4") (pintype "bidirectional"))
      (node (ref "U1") (pin "D20") (pinfunction "PMIC_IN_PB_IN_D20") (pintype "bidirectional"))
    )
    (net (code "66") (name "Net-(U1A-PMIC_IN_PWR_EN)") (class "Default")
      (node (ref "PWREN") (pin "TP") (pinfunction "TP_TP") (pintype "input"))
      (node (ref "U1") (pin "C6") (pinfunction "PMIC_POWER_EN_C6") (pintype "output"))
      (node (ref "U1") (pin "D19") (pinfunction "PMIC_IN_PWR_EN_D19") (pintype "input"))
    )
    (net (code "67") (name "Net-(U1A-PMIC_OUT_LDO_PGOOD)") (class "Default")
      (node (ref "LPGD") (pin "TP") (pinfunction "TP_TP") (pintype "input"))
      (node (ref "U1") (pin "B20") (pinfunction "PMIC_OUT_LDO_PGOOD_B20") (pintype "output"))
      (node (ref "U1") (pin "B5") (pinfunction "RTC_PWRONRSTN_B5") (pintype "bidirectional"))
    )
    (net (code "68") (name "Net-(U1A-PMIC_OUT_PGOOD)") (class "Default")
      (node (ref "PGD") (pin "TP") (pinfunction "TP_TP") (pintype "input"))
      (node (ref "U1") (pin "A20") (pinfunction "PMIC_OUT_PGOOD_A20") (pintype "output"))
      (node (ref "U1") (pin "B15") (pinfunction "PWRONRSTN_B15") (pintype "bidirectional"))
      (node (ref "U3") (pin "2") (pinfunction "A_2") (pintype "input"))
    )
    (net (code "69") (name "Net-(U1A-RTC_KALDO_ENN)") (class "Default")
      (node (ref "R13") (pin "1") (pinfunction "1_1") (pintype "passive"))
      (node (ref "U1") (pin "B4") (pinfunction "RTC_KALDO_ENN_B4") (pintype "bidirectional"))
    )
    (net (code "70") (name "Net-(U1B-AIN2)") (class "Default")
      (node (ref "AIN2") (pin "P$1") (pinfunction "P$1_P$1") (pintype "bidirectional"))
      (node (ref "U1") (pin "B7") (pinfunction "AIN2_B7") (pintype "bidirectional"))
    )
    (net (code "71") (name "Net-(U1B-AIN3)") (class "Default")
      (node (ref "AIN3") (pin "P$1") (pinfunction "P$1_P$1") (pintype "bidirectional"))
      (node (ref "U1") (pin "A7") (pinfunction "AIN3_A7") (pintype "bidirectional"))
    )
    (net (code "72") (name "Net-(U1B-AIN5)") (class "Default")
      (node (ref "AIN5") (pin "P$1") (pinfunction "P$1_P$1") (pintype "bidirectional"))
      (node (ref "U1") (pin "B8") (pinfunction "AIN5_B8") (pintype "bidirectional"))
    )
    (net (code "73") (name "Net-(U1B-AIN6)") (class "Default")
      (node (ref "AIN6") (pin "P$1") (pinfunction "P$1_P$1") (pintype "bidirectional"))
      (node (ref "U1") (pin "A8") (pinfunction "AIN6_A8") (pintype "bidirectional"))
    )
    (net (code "74") (name "Net-(U1B-OSC0_GND)") (class "Default")
      (node (ref "C4") (pin "1") (pinfunction "1_1") (pintype "passive"))
      (node (ref "C5") (pin "1") (pinfunction "1_1") (pintype "passive"))
      (node (ref "U1") (pin "L20") (pinfunction "OSC0_GND_L20") (pintype "bidirectional"))
    )
    (net (code "75") (name "Net-(U1B-OSC0_IN)") (class "Default")
      (node (ref "C4") (pin "2") (pinfunction "2_2") (pintype "passive"))
      (node (ref "R11") (pin "2") (pinfunction "2_2") (pintype "passive"))
      (node (ref "U1") (pin "M20") (pinfunction "OSC0_IN_M20") (pintype "bidirectional"))
      (node (ref "Y1") (pin "P$1") (pinfunction "1_P$1") (pintype "passive"))
    )
    (net (code "76") (name "Net-(U1B-OSC0_OUT)") (class "Default")
      (node (ref "C5") (pin "2") (pinfunction "2_2") (pintype "passive"))
      (node (ref "R11") (pin "1") (pinfunction "1_1") (pintype "passive"))
      (node (ref "U1") (pin "K20") (pinfunction "OSC0_OUT_K20") (pintype "bidirectional"))
      (node (ref "Y1") (pin "P$2") (pinfunction "2_P$2") (pintype "passive"))
    )
    (net (code "77") (name "Net-(U1B-OSC1_GND)") (class "Default")
      (node (ref "C6") (pin "1") (pinfunction "1_1") (pintype "passive"))
      (node (ref "C7") (pin "1") (pinfunction "1_1") (pintype "passive"))
      (node (ref "U1") (pin "G20") (pinfunction "OSC1_GND_G20") (pintype "bidirectional"))
    )
    (net (code "78") (name "Net-(U1B-OSC1_IN)") (class "Default")
      (node (ref "C6") (pin "2") (pinfunction "2_2") (pintype "passive"))
      (node (ref "R12") (pin "2") (pinfunction "2_2") (pintype "passive"))
      (node (ref "U1") (pin "H20") (pinfunction "OSC1_IN_H20") (pintype "bidirectional"))
      (node (ref "Y2") (pin "P$2") (pinfunction "P$2_P$2") (pintype "passive"))
    )
    (net (code "79") (name "Net-(U1B-OSC1_OUT)") (class "Default")
      (node (ref "C7") (pin "2") (pinfunction "2_2") (pintype "passive"))
      (node (ref "R12") (pin "1") (pinfunction "1_1") (pintype "passive"))
      (node (ref "U1") (pin "F20") (pinfunction "OSC1_OUT_F20") (pintype "bidirectional"))
      (node (ref "Y2") (pin "P$1") (pinfunction "P$1_P$1") (pintype "passive"))
    )
    (net (code "80") (name "Net-(U1B-VREFP)") (class "Default")
      (node (ref "C1") (pin "2") (pinfunction "2_2") (pintype "passive"))
      (node (ref "C2") (pin "2") (pinfunction "2_2") (pintype "passive"))
      (node (ref "C3") (pin "2") (pinfunction "2_2") (pintype "passive"))
      (node (ref "R2") (pin "2") (pinfunction "2_2") (pintype "passive"))
      (node (ref "U1") (pin "B9") (pinfunction "VREFP_B9") (pintype "bidirectional"))
    )
    (net (code "81") (name "Net-(U1C-GPMC_A00)") (class "Default")
      (node (ref "U$1") (pin "P$1") (pinfunction "P$1_P$1") (pintype "bidirectional"))
      (node (ref "U1") (pin "R13") (pinfunction "GPMC_A00_R13") (pintype "bidirectional"))
    )
    (net (code "82") (name "Net-(U1C-GPMC_A03)") (class "Default")
      (node (ref "U$6") (pin "P$1") (pinfunction "P$1_P$1") (pintype "bidirectional"))
      (node (ref "U1") (pin "T14") (pinfunction "GPMC_A03_T14") (pintype "bidirectional"))
    )
    (net (code "83") (name "Net-(U1C-GPMC_A09)") (class "Default")
      (node (ref "S3") (pin "1") (pinfunction "1_1") (pintype "bidirectional"))
      (node (ref "S3") (pin "3") (pinfunction "3_3") (pintype "bidirectional"))
      (node (ref "U1") (pin "U16") (pinfunction "GPMC_A09_U16") (pintype "bidirectional"))
    )
    (net (code "84") (name "Net-(U1C-GPMC_A11)") (class "Default")
      (node (ref "S4") (pin "1") (pinfunction "1_1") (pintype "bidirectional"))
      (node (ref "S4") (pin "3") (pinfunction "3_3") (pintype "bidirectional"))
      (node (ref "U1") (pin "V17") (pinfunction "GPMC_A11_V17") (pintype "bidirectional"))
    )
    (net (code "85") (name "Net-(U1C-GPMC_AD08)") (class "Default")
      (node (ref "U$12") (pin "P$1") (pinfunction "P$1_P$1") (pintype "bidirectional"))
      (node (ref "U1") (pin "U10") (pinfunction "GPMC_AD08_U10") (pintype "bidirectional"))
    )
    (net (code "86") (name "Net-(U1C-GPMC_AD09)") (class "Default")
      (node (ref "U$13") (pin "P$1") (pinfunction "P$1_P$1") (pintype "bidirectional"))
      (node (ref "U1") (pin "T10") (pinfunction "GPMC_AD09_T10") (pintype "bidirectional"))
    )
    (net (code "87") (name "Net-(U1C-GPMC_AD12)") (class "Default")
      (node (ref "U$4") (pin "P$1") (pinfunction "P$1_P$1") (pintype "bidirectional"))
      (node (ref "U1") (pin "T12") (pinfunction "GPMC_AD12_T12") (pintype "bidirectional"))
    )
    (net (code "88") (name "Net-(U1C-GPMC_AD13)") (class "Default")
      (node (ref "U$5") (pin "P$1") (pinfunction "P$1_P$1") (pintype "bidirectional"))
      (node (ref "U1") (pin "R12") (pinfunction "GPMC_AD13_R12") (pintype "bidirectional"))
    )
    (net (code "89") (name "Net-(U1C-GPMC_CSN1)") (class "Default")
      (node (ref "R55") (pin "1") (pinfunction "1_1") (pintype "passive"))
      (node (ref "U1") (pin "U9") (pinfunction "GPMC_CSN1_U9") (pintype "bidirectional"))
    )
    (net (code "90") (name "Net-(U1C-MCASP0_ACLKR)") (class "Default")
      (node (ref "U$8") (pin "P$1") (pinfunction "P$1_P$1") (pintype "bidirectional"))
      (node (ref "U1") (pin "B12") (pinfunction "MCASP0_ACLKR_B12") (pintype "bidirectional"))
    )
    (net (code "91") (name "Net-(U1C-MCASP0_ACLKX)") (class "Default")
      (node (ref "U$10") (pin "P$1") (pinfunction "P$1_P$1") (pintype "bidirectional"))
      (node (ref "U1") (pin "A13") (pinfunction "MCASP0_ACLKX_A13") (pintype "bidirectional"))
    )
    (net (code "92") (name "Net-(U1C-MCASP0_AHCLKX)") (class "Default")
      (node (ref "U$11") (pin "P$1") (pinfunction "P$1_P$1") (pintype "bidirectional"))
      (node (ref "U1") (pin "A14") (pinfunction "MCASP0_AHCLKX_A14") (pintype "bidirectional"))
    )
    (net (code "93") (name "Net-(U1C-MCASP0_FSR)") (class "Default")
      (node (ref "U$7") (pin "P$1") (pinfunction "P$1_P$1") (pintype "bidirectional"))
      (node (ref "U1") (pin "C13") (pinfunction "MCASP0_FSR_C13") (pintype "bidirectional"))
    )
    (net (code "94") (name "Net-(U1C-SPI0_CS0)") (class "Default")
      (node (ref "SPI0_CS") (pin "P$1") (pinfunction "P$1_P$1") (pintype "bidirectional"))
      (node (ref "U1") (pin "A16") (pinfunction "SPI0_CS0_A16") (pintype "bidirectional"))
    )
    (net (code "95") (name "Net-(U1C-SPI0_D0)") (class "Default")
      (node (ref "SPI0_MISO") (pin "P$1") (pinfunction "P$1_P$1") (pintype "bidirectional"))
      (node (ref "U1") (pin "B17") (pinfunction "SPI0_D0_B17") (pintype "bidirectional"))
    )
    (net (code "96") (name "Net-(U1C-SPI0_D1)") (class "Default")
      (node (ref "SPI0_MOSI") (pin "P$1") (pinfunction "P$1_P$1") (pintype "bidirectional"))
      (node (ref "U1") (pin "B16") (pinfunction "SPI0_D1_B16") (pintype "bidirectional"))
    )
    (net (code "97") (name "Net-(U1C-SPI0_SCLK)") (class "Default")
      (node (ref "SPI0_SCK") (pin "P$1") (pinfunction "P$1_P$1") (pintype "bidirectional"))
      (node (ref "U1") (pin "A17") (pinfunction "SPI0_SCLK_A17") (pintype "bidirectional"))
    )
    (net (code "98") (name "Net-(U1C-UART0_RXD)") (class "Default")
      (node (ref "U1") (pin "E15") (pinfunction "UART0_RXD_E15") (pintype "bidirectional"))
      (node (ref "UART0_RXD") (pin "P$1") (pinfunction "P$1_P$1") (pintype "bidirectional"))
    )
    (net (code "99") (name "Net-(U1C-UART0_TXD)") (class "Default")
      (node (ref "U1") (pin "E16") (pinfunction "UART0_TXD_E16") (pintype "bidirectional"))
      (node (ref "UART0_TXD") (pin "P$1") (pinfunction "P$1_P$1") (pintype "bidirectional"))
    )
    (net (code "100") (name "Net-(U2-CATHODE)") (class "Default")
      (node (ref "Q1") (pin "B") (pinfunction "B_B") (pintype "passive"))
      (node (ref "R6") (pin "1") (pinfunction "1_1") (pintype "passive"))
      (node (ref "U2") (pin "2") (pinfunction "CATHODE_2") (pintype "bidirectional"))
    )
    (net (code "101") (name "Net-(U2-REF)") (class "Default")
      (node (ref "R7") (pin "1") (pinfunction "1_1") (pintype "passive"))
      (node (ref "R8") (pin "2") (pinfunction "2_2") (pintype "passive"))
      (node (ref "U2") (pin "1") (pinfunction "REF_1") (pintype "bidirectional"))
    )
    (net (code "102") (name "Net-(U3-Y)") (class "Default")
      (node (ref "S2") (pin "1") (pinfunction "1_1") (pintype "bidirectional"))
      (node (ref "S2") (pin "3") (pinfunction "3_3") (pintype "bidirectional"))
      (node (ref "U3") (pin "4") (pinfunction "Y_4") (pintype "output"))
      (node (ref "U4") (pin "3") (pinfunction "MR#_3") (pintype "bidirectional"))
    )
    (net (code "103") (name "Net-(U4-RESET#)") (class "Default")
      (node (ref "R9") (pin "1") (pinfunction "1_1") (pintype "passive"))
      (node (ref "U4") (pin "2") (pinfunction "RESET#_2") (pintype "bidirectional"))
    )
    (net (code "104") (name "Net-(U8-WP)") (class "Default")
      (node (ref "R56") (pin "1") (pinfunction "1_1") (pintype "passive"))
      (node (ref "U8") (pin "5") (pinfunction "WP_5") (pintype "bidirectional"))
      (node (ref "WP") (pin "P$1") (pinfunction "TP_P$1") (pintype "bidirectional"))
    )
    (net (code "105") (name "Net-(VDDSHV_3P3V-TP)") (class "Default")
      (node (ref "U1") (pin "E10") (pinfunction "VDDSHV_3P3V_E10") (pintype "bidirectional"))
      (node (ref "VDDSHV_3P3V") (pin "P$1") (pinfunction "TP_P$1") (pintype "bidirectional"))
    )
    (net (code "106") (name "Net-(VDDS_DDR-TP)") (class "Default")
      (node (ref "U1") (pin "E5") (pinfunction "VDDS_DDR_E5") (pintype "bidirectional"))
      (node (ref "VDDS_DDR") (pin "P$1") (pinfunction "TP_P$1") (pintype "bidirectional"))
    )
    (net (code "107") (name "Net-(VDDS_PLL-TP)") (class "Default")
      (node (ref "U1") (pin "E7") (pinfunction "VDDS_PLL_E7") (pintype "bidirectional"))
      (node (ref "VDDS_PLL") (pin "P$1") (pinfunction "TP_P$1") (pintype "bidirectional"))
    )
    (net (code "108") (name "Net-(VDD_CORE-TP)") (class "Default")
      (node (ref "U1") (pin "F6") (pinfunction "VDD_CORE_F6") (pintype "bidirectional"))
      (node (ref "VDD_CORE") (pin "P$1") (pinfunction "TP_P$1") (pintype "bidirectional"))
    )
    (net (code "109") (name "Net-(VDD_MPU-TP)") (class "Default")
      (node (ref "U1") (pin "F10") (pinfunction "VDD_MPU_F10") (pintype "bidirectional"))
      (node (ref "VDD_MPU") (pin "P$1") (pinfunction "TP_P$1") (pintype "bidirectional"))
    )
    (net (code "110") (name "Net-(X3-VBUS)") (class "Default")
      (node (ref "FB2") (pin "2") (pinfunction "2_2") (pintype "passive"))
      (node (ref "X3") (pin "1") (pinfunction "VBUS_1") (pintype "bidirectional"))
    )
    (net (code "111") (name "SYS_ADC_1P8V") (class "Default")
      (node (ref "R2") (pin "1") (pinfunction "1_1") (pintype "passive"))
      (node (ref "U1") (pin "A4") (pinfunction "SYS_ADC_1P8V_A4") (pintype "bidirectional"))
      (node (ref "U1") (pin "A5") (pinfunction "SYS_ADC_1P8V_A5") (pintype "bidirectional"))
      (node (ref "U1") (pin "D8") (pinfunction "SYS_ADC_1P8V_D8") (pintype "bidirectional"))
      (node (ref "VDD_ADC") (pin "P$1") (pinfunction "TP_P$1") (pintype "bidirectional"))
    )
    (net (code "112") (name "SYS_RSTN") (class "Default")
      (node (ref "C9") (pin "2") (pinfunction "2_2") (pintype "passive"))
      (node (ref "JTAG") (pin "15") (pinfunction "SRST_15") (pintype "bidirectional"))
      (node (ref "R10") (pin "2") (pinfunction "2_2") (pintype "passive"))
      (node (ref "R9") (pin "2") (pinfunction "2_2") (pintype "passive"))
      (node (ref "U1") (pin "A10") (pinfunction "WARMRSTN_A10") (pintype "bidirectional"))
      (node (ref "WRST") (pin "TP") (pinfunction "TP_TP") (pintype "input"))
    )
    (net (code "113") (name "SYS_RTC_1P8V") (class "Default")
      (node (ref "Q1") (pin "C") (pinfunction "C_C") (pintype "passive"))
      (node (ref "R8") (pin "1") (pinfunction "1_1") (pintype "passive"))
      (node (ref "U1") (pin "P14") (pinfunction "SYS_RTC_1P8V_P14") (pintype "bidirectional"))
      (node (ref "U1") (pin "P9") (pinfunction "SYS_RTC_1P8V_P9") (pintype "bidirectional"))
      (node (ref "U2") (pin "3") (pinfunction "ANODE_3") (pintype "bidirectional"))
      (node (ref "U3") (pin "5") (pinfunction "VCC_5") (pintype "power_in"))
    )
    (net (code "114") (name "SYS_VDD1_3P3V") (class "Default")
      (node (ref "C13") (pin "1") (pinfunction "1_1") (pintype "passive"))
      (node (ref "C14") (pin "1") (pinfunction "1_1") (pintype "passive"))
      (node (ref "C15") (pin "1") (pinfunction "1_1") (pintype "passive"))
      (node (ref "C16") (pin "1") (pinfunction "1_1") (pintype "passive"))
      (node (ref "C17") (pin "1") (pinfunction "1_1") (pintype "passive"))
      (node (ref "C18") (pin "1") (pinfunction "1_1") (pintype "passive"))
      (node (ref "C19") (pin "1") (pinfunction "1_1") (pintype "passive"))
      (node (ref "C21") (pin "1") (pinfunction "1_1") (pintype "passive"))
      (node (ref "C8") (pin "2") (pinfunction "2_2") (pintype "passive"))
      (node (ref "IC1") (pin "C6") (pinfunction "VCCQ1_C6") (pintype "bidirectional"))
      (node (ref "IC1") (pin "E6") (pinfunction "VCC1_E6") (pintype "bidirectional"))
      (node (ref "IC1") (pin "F5") (pinfunction "VCC2_F5") (pintype "bidirectional"))
      (node (ref "IC1") (pin "J10") (pinfunction "VCC3_J10") (pintype "bidirectional"))
      (node (ref "IC1") (pin "K9") (pinfunction "VCC4_K9") (pintype "bidirectional"))
      (node (ref "IC1") (pin "M4") (pinfunction "VCCQ2_M4") (pintype "bidirectional"))
      (node (ref "IC1") (pin "N4") (pinfunction "VCCQ3_N4") (pintype "bidirectional"))
      (node (ref "IC1") (pin "P3") (pinfunction "VCCQ4_P3") (pintype "bidirectional"))
      (node (ref "IC1") (pin "P5") (pinfunction "VCCQ5_P5") (pintype "bidirectional"))
      (node (ref "J1") (pin "4") (pinfunction "VDD_4") (pintype "power_in"))
      (node (ref "JTAG") (pin "5") (pinfunction "TVDD_5") (pintype "bidirectional"))
      (node (ref "R14") (pin "2") (pinfunction "2_2") (pintype "passive"))
      (node (ref "R16") (pin "2") (pinfunction "2_2") (pintype "passive"))
      (node (ref "R20") (pin "2") (pinfunction "2_2") (pintype "passive"))
      (node (ref "R21") (pin "2") (pinfunction "2_2") (pintype "passive"))
      (node (ref "R3") (pin "2") (pinfunction "2_2") (pintype "passive"))
      (node (ref "R31") (pin "2") (pinfunction "2_2") (pintype "passive"))
      (node (ref "R35") (pin "2") (pinfunction "2_2") (pintype "passive"))
      (node (ref "R37") (pin "2") (pinfunction "2_2") (pintype "passive"))
      (node (ref "R38") (pin "2") (pinfunction "2_2") (pintype "passive"))
      (node (ref "R39") (pin "2") (pinfunction "2_2") (pintype "passive"))
      (node (ref "R4") (pin "2") (pinfunction "2_2") (pintype "passive"))
      (node (ref "R40") (pin "2") (pinfunction "2_2") (pintype "passive"))
      (node (ref "R41") (pin "2") (pinfunction "2_2") (pintype "passive"))
      (node (ref "R42") (pin "2") (pinfunction "2_2") (pintype "passive"))
      (node (ref "R43") (pin "2") (pinfunction "2_2") (pintype "passive"))
      (node (ref "R44") (pin "2") (pinfunction "2_2") (pintype "passive"))
      (node (ref "R45") (pin "2") (pinfunction "2_2") (pintype "passive"))
      (node (ref "R46") (pin "2") (pinfunction "2_2") (pintype "passive"))
      (node (ref "R47") (pin "2") (pinfunction "2_2") (pintype "passive"))
      (node (ref "R48") (pin "2") (pinfunction "2_2") (pintype "passive"))
      (node (ref "R49") (pin "2") (pinfunction "2_2") (pintype "passive"))
      (node (ref "R50") (pin "2") (pinfunction "2_2") (pintype "passive"))
      (node (ref "R51") (pin "2") (pinfunction "2_2") (pintype "passive"))
      (node (ref "R52") (pin "2") (pinfunction "2_2") (pintype "passive"))
      (node (ref "R53") (pin "2") (pinfunction "2_2") (pintype "passive"))
      (node (ref "R54") (pin "2") (pinfunction "2_2") (pintype "passive"))
      (node (ref "R56") (pin "2") (pinfunction "2_2") (pintype "passive"))
      (node (ref "SYS_VDD1_3P3V") (pin "P$1") (pinfunction "TP_P$1") (pintype "bidirectional"))
      (node (ref "U1") (pin "U20") (pinfunction "SYS_VDD1_3P3V_U20") (pintype "bidirectional"))
      (node (ref "U1") (pin "V20") (pinfunction "SYS_VDD1_3P3V_V20") (pintype "bidirectional"))
      (node (ref "U4") (pin "4") (pinfunction "VCC_4") (pintype "bidirectional"))
      (node (ref "U8") (pin "4") (pinfunction "VCC_4") (pintype "bidirectional"))
    )
    (net (code "115") (name "SYS_VDD2_3P3V") (class "Default")
      (node (ref "R5") (pin "2") (pinfunction "2_2") (pintype "passive"))
      (node (ref "SYS_VDD2_3P3V") (pin "P$1") (pinfunction "TP_P$1") (pintype "bidirectional"))
      (node (ref "U1") (pin "Y11") (pinfunction "SYS_VDD2_3P3V_Y11") (pintype "bidirectional"))
    )
    (net (code "116") (name "SYS_VDD_1P8V") (class "Default")
      (node (ref "U1") (pin "R16") (pinfunction "SYS_VDD_1P8V_R16") (pintype "bidirectional"))
    )
    (net (code "117") (name "SYS_VOUT") (class "Default")
      (node (ref "C11") (pin "+") (pinfunction "+_+") (pintype "passive"))
      (node (ref "SYS_VOUT") (pin "P$1") (pinfunction "TP_P$1") (pintype "bidirectional"))
      (node (ref "U1") (pin "W4") (pinfunction "SYS_VOUT_W4") (pintype "bidirectional"))
      (node (ref "U1") (pin "Y4") (pinfunction "SYS_VOUT_Y4") (pintype "bidirectional"))
      (node (ref "U5") (pin "2") (pinfunction "IN1_2") (pintype "input"))
      (node (ref "U5") (pin "3") (pinfunction "IN2_3") (pintype "input"))
    )
    (net (code "118") (name "USB0_DM") (class "Default")
      (node (ref "U1") (pin "N18") (pinfunction "USB0_DM_N18") (pintype "bidirectional"))
      (node (ref "U7") (pin "1") (pinfunction "D-_1") (pintype "passive"))
      (node (ref "X2") (pin "D-") (pinfunction "D-_D-") (pintype "input"))
    )
    (net (code "119") (name "USB0_DP") (class "Default")
      (node (ref "U1") (pin "N17") (pinfunction "USB0_DP_N17") (pintype "bidirectional"))
      (node (ref "U7") (pin "2") (pinfunction "D+_2") (pintype "passive"))
      (node (ref "X2") (pin "D+") (pinfunction "D+_D+") (pintype "input"))
    )
    (net (code "120") (name "USB0_ID") (class "Default")
      (node (ref "U1") (pin "P16") (pinfunction "USB0_ID_P16") (pintype "bidirectional"))
      (node (ref "U7") (pin "3") (pinfunction "ID_3") (pintype "passive"))
      (node (ref "X2") (pin "ID") (pinfunction "ID_ID") (pintype "input"))
    )
    (net (code "121") (name "USB1_DM") (class "Default")
      (node (ref "U1") (pin "R18") (pinfunction "USB1_DM_R18") (pintype "bidirectional"))
      (node (ref "U6") (pin "1") (pinfunction "D-_1") (pintype "passive"))
      (node (ref "X3") (pin "2") (pinfunction "D-_2") (pintype "bidirectional"))
    )
    (net (code "122") (name "USB1_DP") (class "Default")
      (node (ref "U1") (pin "R17") (pinfunction "USB1_DP_R17") (pintype "bidirectional"))
      (node (ref "U6") (pin "2") (pinfunction "D+_2") (pintype "passive"))
      (node (ref "X3") (pin "3") (pinfunction "D+_3") (pintype "bidirectional"))
    )
    (net (code "123") (name "USB1_DRVVBUS") (class "Default")
      (node (ref "R34") (pin "2") (pinfunction "2_2") (pintype "passive"))
      (node (ref "U1") (pin "F15") (pinfunction "USB1_DRVVBUS_F15") (pintype "bidirectional"))
      (node (ref "U5") (pin "4") (pinfunction "EN_4") (pintype "input"))
    )
    (net (code "124") (name "USB1_OCN") (class "Default")
      (node (ref "R35") (pin "1") (pinfunction "1_1") (pintype "passive"))
      (node (ref "U1") (pin "T16") (pinfunction "GPMC_A10_T16") (pintype "bidirectional"))
      (node (ref "U5") (pin "5") (pinfunction "~{OC}_5") (pintype "output"))
    )
    (net (code "125") (name "USB1_PWR") (class "Default")
      (node (ref "C10") (pin "1") (pinfunction "1_1") (pintype "passive"))
      (node (ref "FB1") (pin "2") (pinfunction "2_2") (pintype "passive"))
      (node (ref "FB2") (pin "1") (pinfunction "1_1") (pintype "passive"))
      (node (ref "U5") (pin "6") (pinfunction "OUT1_6") (pintype "output"))
      (node (ref "U5") (pin "7") (pinfunction "OUT2_7") (pintype "output"))
      (node (ref "U5") (pin "8") (pinfunction "OUT3_8") (pintype "output"))
      (node (ref "U6") (pin "6") (pinfunction "VBUS_6") (pintype "passive"))
    )
    (net (code "126") (name "USB1_VBUS") (class "Default")
      (node (ref "FB1") (pin "1") (pinfunction "1_1") (pintype "passive"))
      (node (ref "U1") (pin "T18") (pinfunction "USB1_VBUS_T18") (pintype "bidirectional"))
    )
    (net (code "127") (name "USB_DC") (class "Default")
      (node (ref "C12") (pin "1") (pinfunction "1_1") (pintype "passive"))
      (node (ref "R36") (pin "1") (pinfunction "1_1") (pintype "passive"))
      (node (ref "U1") (pin "P15") (pinfunction "USB0_VBUS_P15") (pintype "bidirectional"))
      (node (ref "U1") (pin "Y8") (pinfunction "VIN_USB_Y8") (pintype "bidirectional"))
      (node (ref "U1") (pin "Y9") (pinfunction "VIN_USB_Y9") (pintype "bidirectional"))
      (node (ref "U7") (pin "6") (pinfunction "VBUS_6") (pintype "passive"))
      (node (ref "USB_DC") (pin "P$1") (pinfunction "TP_P$1") (pintype "bidirectional"))
    )
    (net (code "128") (name "USR0") (class "Default")
      (node (ref "D3") (pin "1") (pinfunction "A_1") (pintype "passive"))
      (node (ref "U1") (pin "V15") (pinfunction "GPMC_A05_V15") (pintype "bidirectional"))
    )
    (net (code "129") (name "USR1") (class "Default")
      (node (ref "D4") (pin "1") (pinfunction "A_1") (pintype "passive"))
      (node (ref "U1") (pin "U15") (pinfunction "GPMC_A06_U15") (pintype "bidirectional"))
    )
    (net (code "130") (name "USR2") (class "Default")
      (node (ref "D5") (pin "1") (pinfunction "A_1") (pintype "passive"))
      (node (ref "U1") (pin "T15") (pinfunction "GPMC_A07_T15") (pintype "bidirectional"))
    )
    (net (code "131") (name "USR3") (class "Default")
      (node (ref "D6") (pin "1") (pinfunction "A_1") (pintype "passive"))
      (node (ref "U1") (pin "V16") (pinfunction "GPMC_A08_V16") (pintype "bidirectional"))
    )
    (net (code "132") (name "VDDSHV_3P3V") (class "Default")
      (node (ref "Q1") (pin "E") (pinfunction "E_E") (pintype "passive"))
      (node (ref "R6") (pin "2") (pinfunction "2_2") (pintype "passive"))
      (node (ref "R7") (pin "2") (pinfunction "2_2") (pintype "passive"))
      (node (ref "U1") (pin "R15") (pinfunction "VDDSHV_3P3V_R15") (pintype "bidirectional"))
    )
    (net (code "133") (name "VDD_5V") (class "Default")
      (node (ref "U1") (pin "Y5") (pinfunction "VIN_AC_Y5") (pintype "bidirectional"))
      (node (ref "U1") (pin "Y6") (pinfunction "VIN_AC_Y6") (pintype "bidirectional"))
      (node (ref "VDD_5V") (pin "P$1") (pinfunction "TP_P$1") (pintype "bidirectional"))
      (node (ref "X1") (pin "IN") (pinfunction "IN_IN") (pintype "bidirectional"))
    )
    (net (code "134") (name "unconnected-(JTAG-NC-Pad6)") (class "Default")
      (node (ref "JTAG") (pin "6") (pinfunction "NC_6") (pintype "bidirectional"))
    )
    (net (code "135") (name "unconnected-(U1A-SYS_RTC_1P8V-PadE6)") (class "Default")
      (node (ref "U1") (pin "E6") (pinfunction "SYS_RTC_1P8V_E6") (pintype "bidirectional"))
    )
    (net (code "136") (name "unconnected-(U1A-SYS_RTC_1P8V-PadE14)") (class "Default")
      (node (ref "U1") (pin "E14") (pinfunction "SYS_RTC_1P8V_E14") (pintype "bidirectional"))
    )
    (net (code "137") (name "unconnected-(U1A-SYS_RTC_1P8V-PadF9)") (class "Default")
      (node (ref "U1") (pin "F9") (pinfunction "SYS_RTC_1P8V_F9") (pintype "bidirectional"))
    )
    (net (code "138") (name "unconnected-(U1A-SYS_RTC_1P8V-PadK13)") (class "Default")
      (node (ref "U1") (pin "K13") (pinfunction "SYS_RTC_1P8V_K13") (pintype "bidirectional"))
    )
    (net (code "139") (name "unconnected-(U1A-SYS_RTC_1P8V-PadN6)") (class "Default")
      (node (ref "U1") (pin "N6") (pinfunction "SYS_RTC_1P8V_N6") (pintype "bidirectional"))
    )
    (net (code "140") (name "unconnected-(U1A-SYS_VDD_1P8V-PadD10)") (class "Default")
      (node (ref "U1") (pin "D10") (pinfunction "SYS_VDD_1P8V_D10") (pintype "bidirectional"))
    )
    (net (code "141") (name "unconnected-(U1A-SYS_VDD_1P8V-PadN16)") (class "Default")
      (node (ref "U1") (pin "N16") (pinfunction "SYS_VDD_1P8V_N16") (pintype "bidirectional"))
    )
    (net (code "142") (name "unconnected-(U1B-AIN0-PadB6)") (class "Default")
      (node (ref "U1") (pin "B6") (pinfunction "AIN0_B6") (pintype "bidirectional"))
    )
    (net (code "143") (name "unconnected-(U1B-AIN1-PadC7)") (class "Default")
      (node (ref "U1") (pin "C7") (pinfunction "AIN1_C7") (pintype "bidirectional"))
    )
    (net (code "144") (name "unconnected-(U1B-AIN4-PadC8)") (class "Default")
      (node (ref "U1") (pin "C8") (pinfunction "AIN4_C8") (pintype "bidirectional"))
    )
    (net (code "145") (name "unconnected-(U1B-AIN7-PadC9)") (class "Default")
      (node (ref "U1") (pin "C9") (pinfunction "AIN7_C9") (pintype "bidirectional"))
    )
    (net (code "146") (name "unconnected-(U1B-USB0_CE-PadM15)") (class "Default")
      (node (ref "U1") (pin "M15") (pinfunction "USB0_CE_M15") (pintype "bidirectional"))
    )
    (net (code "147") (name "unconnected-(U1B-USB0_DRVVBUS-PadF16)") (class "Default")
      (node (ref "U1") (pin "F16") (pinfunction "USB0_DRVVBUS_F16") (pintype "bidirectional"))
    )
    (net (code "148") (name "unconnected-(U1B-USB1_CE-PadP18)") (class "Default")
      (node (ref "U1") (pin "P18") (pinfunction "USB1_CE_P18") (pintype "bidirectional"))
    )
    (net (code "149") (name "unconnected-(U1C-ECAP0_IN_PWM0_OUT-PadC18)") (class "Default")
      (node (ref "U1") (pin "C18") (pinfunction "ECAP0_IN_PWM0_OUT_C18") (pintype "bidirectional"))
    )
    (net (code "150") (name "unconnected-(U1C-GPMC_A01-PadV14)") (class "Default")
      (node (ref "U1") (pin "V14") (pinfunction "GPMC_A01_V14") (pintype "bidirectional"))
    )
    (net (code "151") (name "unconnected-(U1C-GPMC_AD10-PadT11)") (class "Default")
      (node (ref "U1") (pin "T11") (pinfunction "GPMC_AD10_T11") (pintype "bidirectional"))
    )
    (net (code "152") (name "unconnected-(U1C-GPMC_AD11-PadU12)") (class "Default")
      (node (ref "U1") (pin "U12") (pinfunction "GPMC_AD11_U12") (pintype "bidirectional"))
    )
    (net (code "153") (name "unconnected-(U1C-GPMC_AD14-PadV13)") (class "Default")
      (node (ref "U1") (pin "V13") (pinfunction "GPMC_AD14_V13") (pintype "bidirectional"))
    )
    (net (code "154") (name "unconnected-(U1C-GPMC_AD15-PadU13)") (class "Default")
      (node (ref "U1") (pin "U13") (pinfunction "GPMC_AD15_U13") (pintype "bidirectional"))
    )
    (net (code "155") (name "unconnected-(U1C-GPMC_ADVN_ALE-PadR7)") (class "Default")
      (node (ref "U1") (pin "R7") (pinfunction "GPMC_ADVN_ALE_R7") (pintype "bidirectional"))
    )
    (net (code "156") (name "unconnected-(U1C-GPMC_BEN0_CLE-PadT6)") (class "Default")
      (node (ref "U1") (pin "T6") (pinfunction "GPMC_BEN0_CLE_T6") (pintype "bidirectional"))
    )
    (net (code "157") (name "unconnected-(U1C-GPMC_BEN1-PadU18)") (class "Default")
      (node (ref "U1") (pin "U18") (pinfunction "GPMC_BEN1_U18") (pintype "bidirectional"))
    )
    (net (code "158") (name "unconnected-(U1C-GPMC_CLK-PadV12)") (class "Default")
      (node (ref "U1") (pin "V12") (pinfunction "GPMC_CLK_V12") (pintype "bidirectional"))
    )
    (net (code "159") (name "unconnected-(U1C-GPMC_CSN0-PadV6)") (class "Default")
      (node (ref "U1") (pin "V6") (pinfunction "GPMC_CSN0_V6") (pintype "bidirectional"))
    )
    (net (code "160") (name "unconnected-(U1C-GPMC_CSN3-PadT13)") (class "Default")
      (node (ref "U1") (pin "T13") (pinfunction "GPMC_CSN3_T13") (pintype "bidirectional"))
    )
    (net (code "161") (name "unconnected-(U1C-GPMC_OEN_REN-PadT7)") (class "Default")
      (node (ref "U1") (pin "T7") (pinfunction "GPMC_OEN_REN_T7") (pintype "bidirectional"))
    )
    (net (code "162") (name "unconnected-(U1C-GPMC_WAIT0-PadT17)") (class "Default")
      (node (ref "U1") (pin "T17") (pinfunction "GPMC_WAIT0_T17") (pintype "bidirectional"))
    )
    (net (code "163") (name "unconnected-(U1C-GPMC_WEN-PadU6)") (class "Default")
      (node (ref "U1") (pin "U6") (pinfunction "GPMC_WEN_U6") (pintype "bidirectional"))
    )
    (net (code "164") (name "unconnected-(U1C-GPMC_WPN-PadU17)") (class "Default")
      (node (ref "U1") (pin "U17") (pinfunction "GPMC_WPN_U17") (pintype "bidirectional"))
    )
    (net (code "165") (name "unconnected-(U1C-MCASP0_AHCLKR-PadC12)") (class "Default")
      (node (ref "U1") (pin "C12") (pinfunction "MCASP0_AHCLKR_C12") (pintype "bidirectional"))
    )
    (net (code "166") (name "unconnected-(U1C-MCASP0_AXR0-PadD12)") (class "Default")
      (node (ref "U1") (pin "D12") (pinfunction "MCASP0_AXR0_D12") (pintype "bidirectional"))
    )
    (net (code "167") (name "unconnected-(U1C-MCASP0_AXR1-PadD13)") (class "Default")
      (node (ref "U1") (pin "D13") (pinfunction "MCASP0_AXR1_D13") (pintype "bidirectional"))
    )
    (net (code "168") (name "unconnected-(U1C-MCASP0_FSX-PadB13)") (class "Default")
      (node (ref "U1") (pin "B13") (pinfunction "MCASP0_FSX_B13") (pintype "bidirectional"))
    )
    (net (code "169") (name "unconnected-(U1C-UART0_CTSN-PadE18)") (class "Default")
      (node (ref "U1") (pin "E18") (pinfunction "UART0_CTSN_E18") (pintype "bidirectional"))
    )
    (net (code "170") (name "unconnected-(U1C-UART0_RTSN-PadE17)") (class "Default")
      (node (ref "U1") (pin "E17") (pinfunction "UART0_RTSN_E17") (pintype "bidirectional"))
    )
    (net (code "171") (name "unconnected-(U1C-UART1_CTSN-PadD18)") (class "Default")
      (node (ref "U1") (pin "D18") (pinfunction "UART1_CTSN_D18") (pintype "bidirectional"))
    )
    (net (code "172") (name "unconnected-(U1C-UART1_RTSN-PadD17)") (class "Default")
      (node (ref "U1") (pin "D17") (pinfunction "UART1_RTSN_D17") (pintype "bidirectional"))
    )
    (net (code "173") (name "unconnected-(U1C-UART1_RXD-PadD16)") (class "Default")
      (node (ref "U1") (pin "D16") (pinfunction "UART1_RXD_D16") (pintype "bidirectional"))
    )
    (net (code "174") (name "unconnected-(U1C-UART1_TXD-PadD15)") (class "Default")
      (node (ref "U1") (pin "D15") (pinfunction "UART1_TXD_D15") (pintype "bidirectional"))
    )
    (net (code "175") (name "unconnected-(U1D-LCD_AC_BIAS_EN-PadR6)") (class "Default")
      (node (ref "U1") (pin "R6") (pinfunction "LCD_AC_BIAS_EN_R6") (pintype "bidirectional"))
    )
    (net (code "176") (name "unconnected-(U1D-LCD_HSYNC-PadR5)") (class "Default")
      (node (ref "U1") (pin "R5") (pinfunction "LCD_HSYNC_R5") (pintype "bidirectional"))
    )
    (net (code "177") (name "unconnected-(U1D-LCD_PCLK-PadV5)") (class "Default")
      (node (ref "U1") (pin "V5") (pinfunction "LCD_PCLK_V5") (pintype "bidirectional"))
    )
    (net (code "178") (name "unconnected-(U1D-LCD_VSYNC-PadU5)") (class "Default")
      (node (ref "U1") (pin "U5") (pinfunction "LCD_VSYNC_U5") (pintype "bidirectional"))
    )
    (net (code "179") (name "unconnected-(U1D-MDC-PadM18)") (class "Default")
      (node (ref "U1") (pin "M18") (pinfunction "MDC_M18") (pintype "bidirectional"))
    )
    (net (code "180") (name "unconnected-(U1D-MDIO-PadM17)") (class "Default")
      (node (ref "U1") (pin "M17") (pinfunction "MDIO_M17") (pintype "bidirectional"))
    )
    (net (code "181") (name "unconnected-(U1D-MII1_COL-PadH16)") (class "Default")
      (node (ref "U1") (pin "H16") (pinfunction "MII1_COL_H16") (pintype "bidirectional"))
    )
    (net (code "182") (name "unconnected-(U1D-MII1_CRS-PadH17)") (class "Default")
      (node (ref "U1") (pin "H17") (pinfunction "MII1_CRS_H17") (pintype "bidirectional"))
    )
    (net (code "183") (name "unconnected-(U1D-MII1_RXD0-PadM16)") (class "Default")
      (node (ref "U1") (pin "M16") (pinfunction "MII1_RXD0_M16") (pintype "bidirectional"))
    )
    (net (code "184") (name "unconnected-(U1D-MII1_RXD1-PadL15)") (class "Default")
      (node (ref "U1") (pin "L15") (pinfunction "MII1_RXD1_L15") (pintype "bidirectional"))
    )
    (net (code "185") (name "unconnected-(U1D-MII1_RXD2-PadL16)") (class "Default")
      (node (ref "U1") (pin "L16") (pinfunction "MII1_RXD2_L16") (pintype "bidirectional"))
    )
    (net (code "186") (name "unconnected-(U1D-MII1_RXD3-PadL17)") (class "Default")
      (node (ref "U1") (pin "L17") (pinfunction "MII1_RXD3_L17") (pintype "bidirectional"))
    )
    (net (code "187") (name "unconnected-(U1D-MII1_RX_CLK-PadL18)") (class "Default")
      (node (ref "U1") (pin "L18") (pinfunction "MII1_RX_CLK_L18") (pintype "bidirectional"))
    )
    (net (code "188") (name "unconnected-(U1D-MII1_RX_DV-PadJ17)") (class "Default")
      (node (ref "U1") (pin "J17") (pinfunction "MII1_RX_DV_J17") (pintype "bidirectional"))
    )
    (net (code "189") (name "unconnected-(U1D-MII1_RX_ER-PadJ15)") (class "Default")
      (node (ref "U1") (pin "J15") (pinfunction "MII1_RX_ER_J15") (pintype "bidirectional"))
    )
    (net (code "190") (name "unconnected-(U1D-MII1_TXD0-PadK17)") (class "Default")
      (node (ref "U1") (pin "K17") (pinfunction "MII1_TXD0_K17") (pintype "bidirectional"))
    )
    (net (code "191") (name "unconnected-(U1D-MII1_TXD1-PadK16)") (class "Default")
      (node (ref "U1") (pin "K16") (pinfunction "MII1_TXD1_K16") (pintype "bidirectional"))
    )
    (net (code "192") (name "unconnected-(U1D-MII1_TXD2-PadK15)") (class "Default")
      (node (ref "U1") (pin "K15") (pinfunction "MII1_TXD2_K15") (pintype "bidirectional"))
    )
    (net (code "193") (name "unconnected-(U1D-MII1_TXD3-PadJ18)") (class "Default")
      (node (ref "U1") (pin "J18") (pinfunction "MII1_TXD3_J18") (pintype "bidirectional"))
    )
    (net (code "194") (name "unconnected-(U1D-MII1_TX_CLK-PadK18)") (class "Default")
      (node (ref "U1") (pin "K18") (pinfunction "MII1_TX_CLK_K18") (pintype "bidirectional"))
    )
    (net (code "195") (name "unconnected-(U1D-MII1_TX_EN-PadJ16)") (class "Default")
      (node (ref "U1") (pin "J16") (pinfunction "MII1_TX_EN_J16") (pintype "bidirectional"))
    )
    (net (code "196") (name "unconnected-(U1D-RMII1_REF_CLK-PadH18)") (class "Default")
      (node (ref "U1") (pin "H18") (pinfunction "RMII1_REF_CLK_H18") (pintype "bidirectional"))
    )
    (net (code "197") (name "unconnected-(U1F-NC-PadB1)") (class "Default")
      (node (ref "U1") (pin "B1") (pinfunction "NC_B1") (pintype "bidirectional"))
    )
    (net (code "198") (name "unconnected-(U1F-NC-PadB2)") (class "Default")
      (node (ref "U1") (pin "B2") (pinfunction "NC_B2") (pintype "bidirectional"))
    )
    (net (code "199") (name "unconnected-(U1F-NC-PadB3)") (class "Default")
      (node (ref "U1") (pin "B3") (pinfunction "NC_B3") (pintype "bidirectional"))
    )
    (net (code "200") (name "unconnected-(U1F-NC-PadC1)") (class "Default")
      (node (ref "U1") (pin "C1") (pinfunction "NC_C1") (pintype "bidirectional"))
    )
    (net (code "201") (name "unconnected-(U1F-NC-PadC2)") (class "Default")
      (node (ref "U1") (pin "C2") (pinfunction "NC_C2") (pintype "bidirectional"))
    )
    (net (code "202") (name "unconnected-(U1F-NC-PadC3)") (class "Default")
      (node (ref "U1") (pin "C3") (pinfunction "NC_C3") (pintype "bidirectional"))
    )
    (net (code "203") (name "unconnected-(U1F-NC-PadC4)") (class "Default")
      (node (ref "U1") (pin "C4") (pinfunction "NC_C4") (pintype "bidirectional"))
    )
    (net (code "204") (name "unconnected-(U1F-NC-PadD1)") (class "Default")
      (node (ref "U1") (pin "D1") (pinfunction "NC_D1") (pintype "bidirectional"))
    )
    (net (code "205") (name "unconnected-(U1F-NC-PadD2)") (class "Default")
      (node (ref "U1") (pin "D2") (pinfunction "NC_D2") (pintype "bidirectional"))
    )
    (net (code "206") (name "unconnected-(U1F-NC-PadD3)") (class "Default")
      (node (ref "U1") (pin "D3") (pinfunction "NC_D3") (pintype "bidirectional"))
    )
    (net (code "207") (name "unconnected-(U1F-NC-PadD4)") (class "Default")
      (node (ref "U1") (pin "D4") (pinfunction "NC_D4") (pintype "bidirectional"))
    )
    (net (code "208") (name "unconnected-(U1F-NC-PadD5)") (class "Default")
      (node (ref "U1") (pin "D5") (pinfunction "NC_D5") (pintype "bidirectional"))
    )
    (net (code "209") (name "unconnected-(U1F-NC-PadE1)") (class "Default")
      (node (ref "U1") (pin "E1") (pinfunction "NC_E1") (pintype "bidirectional"))
    )
    (net (code "210") (name "unconnected-(U1F-NC-PadE2)") (class "Default")
      (node (ref "U1") (pin "E2") (pinfunction "NC_E2") (pintype "bidirectional"))
    )
    (net (code "211") (name "unconnected-(U1F-NC-PadE3)") (class "Default")
      (node (ref "U1") (pin "E3") (pinfunction "NC_E3") (pintype "bidirectional"))
    )
    (net (code "212") (name "unconnected-(U1F-NC-PadE4)") (class "Default")
      (node (ref "U1") (pin "E4") (pinfunction "NC_E4") (pintype "bidirectional"))
    )
    (net (code "213") (name "unconnected-(U1F-NC-PadF1)") (class "Default")
      (node (ref "U1") (pin "F1") (pinfunction "NC_F1") (pintype "bidirectional"))
    )
    (net (code "214") (name "unconnected-(U1F-NC-PadF2)") (class "Default")
      (node (ref "U1") (pin "F2") (pinfunction "NC_F2") (pintype "bidirectional"))
    )
    (net (code "215") (name "unconnected-(U1F-NC-PadF3)") (class "Default")
      (node (ref "U1") (pin "F3") (pinfunction "NC_F3") (pintype "bidirectional"))
    )
    (net (code "216") (name "unconnected-(U1F-NC-PadF4)") (class "Default")
      (node (ref "U1") (pin "F4") (pinfunction "NC_F4") (pintype "bidirectional"))
    )
    (net (code "217") (name "unconnected-(U1F-NC-PadG1)") (class "Default")
      (node (ref "U1") (pin "G1") (pinfunction "NC_G1") (pintype "bidirectional"))
    )
    (net (code "218") (name "unconnected-(U1F-NC-PadG2)") (class "Default")
      (node (ref "U1") (pin "G2") (pinfunction "NC_G2") (pintype "bidirectional"))
    )
    (net (code "219") (name "unconnected-(U1F-NC-PadG3)") (class "Default")
      (node (ref "U1") (pin "G3") (pinfunction "NC_G3") (pintype "bidirectional"))
    )
    (net (code "220") (name "unconnected-(U1F-NC-PadG4)") (class "Default")
      (node (ref "U1") (pin "G4") (pinfunction "NC_G4") (pintype "bidirectional"))
    )
    (net (code "221") (name "unconnected-(U1F-NC-PadH1)") (class "Default")
      (node (ref "U1") (pin "H1") (pinfunction "NC_H1") (pintype "bidirectional"))
    )
    (net (code "222") (name "unconnected-(U1F-NC-PadH2)") (class "Default")
      (node (ref "U1") (pin "H2") (pinfunction "NC_H2") (pintype "bidirectional"))
    )
    (net (code "223") (name "unconnected-(U1F-NC-PadH3)") (class "Default")
      (node (ref "U1") (pin "H3") (pinfunction "NC_H3") (pintype "bidirectional"))
    )
    (net (code "224") (name "unconnected-(U1F-NC-PadH4)") (class "Default")
      (node (ref "U1") (pin "H4") (pinfunction "NC_H4") (pintype "bidirectional"))
    )
    (net (code "225") (name "unconnected-(U1F-NC-PadJ1)") (class "Default")
      (node (ref "U1") (pin "J1") (pinfunction "NC_J1") (pintype "bidirectional"))
    )
    (net (code "226") (name "unconnected-(U1F-NC-PadJ2)") (class "Default")
      (node (ref "U1") (pin "J2") (pinfunction "NC_J2") (pintype "bidirectional"))
    )
    (net (code "227") (name "unconnected-(U1F-NC-PadJ3)") (class "Default")
      (node (ref "U1") (pin "J3") (pinfunction "NC_J3") (pintype "bidirectional"))
    )
    (net (code "228") (name "unconnected-(U1F-NC-PadJ4)") (class "Default")
      (node (ref "U1") (pin "J4") (pinfunction "NC_J4") (pintype "bidirectional"))
    )
    (net (code "229") (name "unconnected-(U1F-NC-PadK1)") (class "Default")
      (node (ref "U1") (pin "K1") (pinfunction "NC_K1") (pintype "bidirectional"))
    )
    (net (code "230") (name "unconnected-(U1F-NC-PadK2)") (class "Default")
      (node (ref "U1") (pin "K2") (pinfunction "NC_K2") (pintype "bidirectional"))
    )
    (net (code "231") (name "unconnected-(U1F-NC-PadK3)") (class "Default")
      (node (ref "U1") (pin "K3") (pinfunction "NC_K3") (pintype "bidirectional"))
    )
    (net (code "232") (name "unconnected-(U1F-NC-PadK4)") (class "Default")
      (node (ref "U1") (pin "K4") (pinfunction "NC_K4") (pintype "bidirectional"))
    )
    (net (code "233") (name "unconnected-(U1F-NC-PadL1)") (class "Default")
      (node (ref "U1") (pin "L1") (pinfunction "NC_L1") (pintype "bidirectional"))
    )
    (net (code "234") (name "unconnected-(U1F-NC-PadL2)") (class "Default")
      (node (ref "U1") (pin "L2") (pinfunction "NC_L2") (pintype "bidirectional"))
    )
    (net (code "235") (name "unconnected-(U1F-NC-PadL3)") (class "Default")
      (node (ref "U1") (pin "L3") (pinfunction "NC_L3") (pintype "bidirectional"))
    )
    (net (code "236") (name "unconnected-(U1F-NC-PadL4)") (class "Default")
      (node (ref "U1") (pin "L4") (pinfunction "NC_L4") (pintype "bidirectional"))
    )
    (net (code "237") (name "unconnected-(U1F-NC-PadM1)") (class "Default")
      (node (ref "U1") (pin "M1") (pinfunction "NC_M1") (pintype "bidirectional"))
    )
    (net (code "238") (name "unconnected-(U1F-NC-PadM2)") (class "Default")
      (node (ref "U1") (pin "M2") (pinfunction "NC_M2") (pintype "bidirectional"))
    )
    (net (code "239") (name "unconnected-(U1F-NC-PadM3)") (class "Default")
      (node (ref "U1") (pin "M3") (pinfunction "NC_M3") (pintype "bidirectional"))
    )
    (net (code "240") (name "unconnected-(U1F-NC-PadM4)") (class "Default")
      (node (ref "U1") (pin "M4") (pinfunction "NC_M4") (pintype "bidirectional"))
    )
    (net (code "241") (name "unconnected-(U1F-NC-PadN1)") (class "Default")
      (node (ref "U1") (pin "N1") (pinfunction "NC_N1") (pintype "bidirectional"))
    )
    (net (code "242") (name "unconnected-(U1F-NC-PadN2)") (class "Default")
      (node (ref "U1") (pin "N2") (pinfunction "NC_N2") (pintype "bidirectional"))
    )
    (net (code "243") (name "unconnected-(U1F-NC-PadN3)") (class "Default")
      (node (ref "U1") (pin "N3") (pinfunction "NC_N3") (pintype "bidirectional"))
    )
    (net (code "244") (name "unconnected-(U1F-NC-PadN4)") (class "Default")
      (node (ref "U1") (pin "N4") (pinfunction "NC_N4") (pintype "bidirectional"))
    )
    (net (code "245") (name "unconnected-(U1F-NC-PadP1)") (class "Default")
      (node (ref "U1") (pin "P1") (pinfunction "NC_P1") (pintype "bidirectional"))
    )
    (net (code "246") (name "unconnected-(U1F-NC-PadP2)") (class "Default")
      (node (ref "U1") (pin "P2") (pinfunction "NC_P2") (pintype "bidirectional"))
    )
    (net (code "247") (name "unconnected-(U1F-NC-PadP3)") (class "Default")
      (node (ref "U1") (pin "P3") (pinfunction "NC_P3") (pintype "bidirectional"))
    )
    (net (code "248") (name "unconnected-(U1F-NC-PadP4)") (class "Default")
      (node (ref "U1") (pin "P4") (pinfunction "NC_P4") (pintype "bidirectional"))
    )
    (net (code "249") (name "unconnected-(U1F-NC-PadU11)") (class "Default")
      (node (ref "U1") (pin "U11") (pinfunction "NC_U11") (pintype "bidirectional"))
    )
    (net (code "250") (name "unconnected-(U1F-NC-PadV10)") (class "Default")
      (node (ref "U1") (pin "V10") (pinfunction "NC_V10") (pintype "bidirectional"))
    )
    (net (code "251") (name "unconnected-(U1F-NC-PadV11)") (class "Default")
      (node (ref "U1") (pin "V11") (pinfunction "NC_V11") (pintype "bidirectional"))
    )
    (net (code "252") (name "unconnected-(U1G-CAP_VBB_MPU-PadC10)") (class "Default")
      (node (ref "U1") (pin "C10") (pinfunction "CAP_VBB_MPU_C10") (pintype "bidirectional"))
    )
    (net (code "253") (name "unconnected-(U1G-CAP_VDD_RTC-PadD6)") (class "Default")
      (node (ref "U1") (pin "D6") (pinfunction "CAP_VDD_RTC_D6") (pintype "bidirectional"))
    )
    (net (code "254") (name "unconnected-(U1G-CAP_VDD_SRAM_CORE-PadD9)") (class "Default")
      (node (ref "U1") (pin "D9") (pinfunction "CAP_VDD_SRAM_CORE_D9") (pintype "bidirectional"))
    )
    (net (code "255") (name "unconnected-(U1G-CAP_VDD_SRAM_MPU-PadD11)") (class "Default")
      (node (ref "U1") (pin "D11") (pinfunction "CAP_VDD_SRAM_MPU_D11") (pintype "bidirectional"))
    )
    (net (code "256") (name "unconnected-(U1G-EXTL1A-PadY13)") (class "Default")
      (node (ref "U1") (pin "Y13") (pinfunction "EXTL1A_Y13") (pintype "bidirectional"))
    )
    (net (code "257") (name "unconnected-(U1G-EXTL1B-PadY14)") (class "Default")
      (node (ref "U1") (pin "Y14") (pinfunction "EXTL1B_Y14") (pintype "bidirectional"))
    )
    (net (code "258") (name "unconnected-(U1G-EXTL2A-PadY16)") (class "Default")
      (node (ref "U1") (pin "Y16") (pinfunction "EXTL2A_Y16") (pintype "bidirectional"))
    )
    (net (code "259") (name "unconnected-(U1G-EXTL2B-PadY17)") (class "Default")
      (node (ref "U1") (pin "Y17") (pinfunction "EXTL2B_Y17") (pintype "bidirectional"))
    )
    (net (code "260") (name "unconnected-(U1G-EXTL3A-PadY19)") (class "Default")
      (node (ref "U1") (pin "Y19") (pinfunction "EXTL3A_Y19") (pintype "bidirectional"))
    )
    (net (code "261") (name "unconnected-(U1G-EXTL3B-PadY20)") (class "Default")
      (node (ref "U1") (pin "Y20") (pinfunction "EXTL3B_Y20") (pintype "bidirectional"))
    )
    (net (code "262") (name "unconnected-(U1G-TESTOUT-PadA3)") (class "Default")
      (node (ref "U1") (pin "A3") (pinfunction "TESTOUT_A3") (pintype "bidirectional"))
    )
    (net (code "263") (name "unconnected-(U1G-VDDSHV_3P3V-PadE11)") (class "Default")
      (node (ref "U1") (pin "E11") (pinfunction "VDDSHV_3P3V_E11") (pintype "bidirectional"))
    )
    (net (code "264") (name "unconnected-(U1G-VDDSHV_3P3V-PadE12)") (class "Default")
      (node (ref "U1") (pin "E12") (pinfunction "VDDSHV_3P3V_E12") (pintype "bidirectional"))
    )
    (net (code "265") (name "unconnected-(U1G-VDDSHV_3P3V-PadE13)") (class "Default")
      (node (ref "U1") (pin "E13") (pinfunction "VDDSHV_3P3V_E13") (pintype "bidirectional"))
    )
    (net (code "266") (name "unconnected-(U1G-VDDSHV_3P3V-PadF14)") (class "Default")
      (node (ref "U1") (pin "F14") (pinfunction "VDDSHV_3P3V_F14") (pintype "bidirectional"))
    )
    (net (code "267") (name "unconnected-(U1G-VDDSHV_3P3V-PadG14)") (class "Default")
      (node (ref "U1") (pin "G14") (pinfunction "VDDSHV_3P3V_G14") (pintype "bidirectional"))
    )
    (net (code "268") (name "unconnected-(U1G-VDDSHV_3P3V-PadH14)") (class "Default")
      (node (ref "U1") (pin "H14") (pinfunction "VDDSHV_3P3V_H14") (pintype "bidirectional"))
    )
    (net (code "269") (name "unconnected-(U1G-VDDSHV_3P3V-PadJ14)") (class "Default")
      (node (ref "U1") (pin "J14") (pinfunction "VDDSHV_3P3V_J14") (pintype "bidirectional"))
    )
    (net (code "270") (name "unconnected-(U1G-VDDSHV_3P3V-PadK14)") (class "Default")
      (node (ref "U1") (pin "K14") (pinfunction "VDDSHV_3P3V_K14") (pintype "bidirectional"))
    )
    (net (code "271") (name "unconnected-(U1G-VDDSHV_3P3V-PadL14)") (class "Default")
      (node (ref "U1") (pin "L14") (pinfunction "VDDSHV_3P3V_L14") (pintype "bidirectional"))
    )
    (net (code "272") (name "unconnected-(U1G-VDDSHV_3P3V-PadN5)") (class "Default")
      (node (ref "U1") (pin "N5") (pinfunction "VDDSHV_3P3V_N5") (pintype "bidirectional"))
    )
    (net (code "273") (name "unconnected-(U1G-VDDSHV_3P3V-PadN15)") (class "Default")
      (node (ref "U1") (pin "N15") (pinfunction "VDDSHV_3P3V_N15") (pintype "bidirectional"))
    )
    (net (code "274") (name "unconnected-(U1G-VDDSHV_3P3V-PadP5)") (class "Default")
      (node (ref "U1") (pin "P5") (pinfunction "VDDSHV_3P3V_P5") (pintype "bidirectional"))
    )
    (net (code "275") (name "unconnected-(U1G-VDDSHV_3P3V-PadP6)") (class "Default")
      (node (ref "U1") (pin "P6") (pinfunction "VDDSHV_3P3V_P6") (pintype "bidirectional"))
    )
    (net (code "276") (name "unconnected-(U1G-VDDSHV_3P3V-PadP7)") (class "Default")
      (node (ref "U1") (pin "P7") (pinfunction "VDDSHV_3P3V_P7") (pintype "bidirectional"))
    )
    (net (code "277") (name "unconnected-(U1G-VDDSHV_3P3V-PadP8)") (class "Default")
      (node (ref "U1") (pin "P8") (pinfunction "VDDSHV_3P3V_P8") (pintype "bidirectional"))
    )
    (net (code "278") (name "unconnected-(U1G-VDDSHV_3P3V-PadP10)") (class "Default")
      (node (ref "U1") (pin "P10") (pinfunction "VDDSHV_3P3V_P10") (pintype "bidirectional"))
    )
    (net (code "279") (name "unconnected-(U1G-VDDSHV_3P3V-PadP11)") (class "Default")
      (node (ref "U1") (pin "P11") (pinfunction "VDDSHV_3P3V_P11") (pintype "bidirectional"))
    )
    (net (code "280") (name "unconnected-(U1G-VDDSHV_3P3V-PadP12)") (class "Default")
      (node (ref "U1") (pin "P12") (pinfunction "VDDSHV_3P3V_P12") (pintype "bidirectional"))
    )
    (net (code "281") (name "unconnected-(U1G-VDDSHV_3P3V-PadP13)") (class "Default")
      (node (ref "U1") (pin "P13") (pinfunction "VDDSHV_3P3V_P13") (pintype "bidirectional"))
    )
    (net (code "282") (name "unconnected-(U1G-VDDS_DDR-PadF5)") (class "Default")
      (node (ref "U1") (pin "F5") (pinfunction "VDDS_DDR_F5") (pintype "bidirectional"))
    )
    (net (code "283") (name "unconnected-(U1G-VDDS_DDR-PadG5)") (class "Default")
      (node (ref "U1") (pin "G5") (pinfunction "VDDS_DDR_G5") (pintype "bidirectional"))
    )
    (net (code "284") (name "unconnected-(U1G-VDDS_DDR-PadH5)") (class "Default")
      (node (ref "U1") (pin "H5") (pinfunction "VDDS_DDR_H5") (pintype "bidirectional"))
    )
    (net (code "285") (name "unconnected-(U1G-VDDS_DDR-PadJ5)") (class "Default")
      (node (ref "U1") (pin "J5") (pinfunction "VDDS_DDR_J5") (pintype "bidirectional"))
    )
    (net (code "286") (name "unconnected-(U1G-VDDS_DDR-PadK5)") (class "Default")
      (node (ref "U1") (pin "K5") (pinfunction "VDDS_DDR_K5") (pintype "bidirectional"))
    )
    (net (code "287") (name "unconnected-(U1G-VDDS_DDR-PadL5)") (class "Default")
      (node (ref "U1") (pin "L5") (pinfunction "VDDS_DDR_L5") (pintype "bidirectional"))
    )
    (net (code "288") (name "unconnected-(U1G-VDDS_PLL-PadH15)") (class "Default")
      (node (ref "U1") (pin "H15") (pinfunction "VDDS_PLL_H15") (pintype "bidirectional"))
    )
    (net (code "289") (name "unconnected-(U1G-VDDS_PLL-PadR10)") (class "Default")
      (node (ref "U1") (pin "R10") (pinfunction "VDDS_PLL_R10") (pintype "bidirectional"))
    )
    (net (code "290") (name "unconnected-(U1G-VDDS_PLL-PadR11)") (class "Default")
      (node (ref "U1") (pin "R11") (pinfunction "VDDS_PLL_R11") (pintype "bidirectional"))
    )
    (net (code "291") (name "unconnected-(U1G-VDD_CORE-PadF7)") (class "Default")
      (node (ref "U1") (pin "F7") (pinfunction "VDD_CORE_F7") (pintype "bidirectional"))
    )
    (net (code "292") (name "unconnected-(U1G-VDD_CORE-PadG6)") (class "Default")
      (node (ref "U1") (pin "G6") (pinfunction "VDD_CORE_G6") (pintype "bidirectional"))
    )
    (net (code "293") (name "unconnected-(U1G-VDD_CORE-PadG7)") (class "Default")
      (node (ref "U1") (pin "G7") (pinfunction "VDD_CORE_G7") (pintype "bidirectional"))
    )
    (net (code "294") (name "unconnected-(U1G-VDD_CORE-PadG10)") (class "Default")
      (node (ref "U1") (pin "G10") (pinfunction "VDD_CORE_G10") (pintype "bidirectional"))
    )
    (net (code "295") (name "unconnected-(U1G-VDD_CORE-PadH11)") (class "Default")
      (node (ref "U1") (pin "H11") (pinfunction "VDD_CORE_H11") (pintype "bidirectional"))
    )
    (net (code "296") (name "unconnected-(U1G-VDD_CORE-PadJ12)") (class "Default")
      (node (ref "U1") (pin "J12") (pinfunction "VDD_CORE_J12") (pintype "bidirectional"))
    )
    (net (code "297") (name "unconnected-(U1G-VDD_CORE-PadK6)") (class "Default")
      (node (ref "U1") (pin "K6") (pinfunction "VDD_CORE_K6") (pintype "bidirectional"))
    )
    (net (code "298") (name "unconnected-(U1G-VDD_CORE-PadK8)") (class "Default")
      (node (ref "U1") (pin "K8") (pinfunction "VDD_CORE_K8") (pintype "bidirectional"))
    )
    (net (code "299") (name "unconnected-(U1G-VDD_CORE-PadK12)") (class "Default")
      (node (ref "U1") (pin "K12") (pinfunction "VDD_CORE_K12") (pintype "bidirectional"))
    )
    (net (code "300") (name "unconnected-(U1G-VDD_CORE-PadL6)") (class "Default")
      (node (ref "U1") (pin "L6") (pinfunction "VDD_CORE_L6") (pintype "bidirectional"))
    )
    (net (code "301") (name "unconnected-(U1G-VDD_CORE-PadL7)") (class "Default")
      (node (ref "U1") (pin "L7") (pinfunction "VDD_CORE_L7") (pintype "bidirectional"))
    )
    (net (code "302") (name "unconnected-(U1G-VDD_CORE-PadL8)") (class "Default")
      (node (ref "U1") (pin "L8") (pinfunction "VDD_CORE_L8") (pintype "bidirectional"))
    )
    (net (code "303") (name "unconnected-(U1G-VDD_CORE-PadL9)") (class "Default")
      (node (ref "U1") (pin "L9") (pinfunction "VDD_CORE_L9") (pintype "bidirectional"))
    )
    (net (code "304") (name "unconnected-(U1G-VDD_CORE-PadM11)") (class "Default")
      (node (ref "U1") (pin "M11") (pinfunction "VDD_CORE_M11") (pintype "bidirectional"))
    )
    (net (code "305") (name "unconnected-(U1G-VDD_CORE-PadM13)") (class "Default")
      (node (ref "U1") (pin "M13") (pinfunction "VDD_CORE_M13") (pintype "bidirectional"))
    )
    (net (code "306") (name "unconnected-(U1G-VDD_CORE-PadN8)") (class "Default")
      (node (ref "U1") (pin "N8") (pinfunction "VDD_CORE_N8") (pintype "bidirectional"))
    )
    (net (code "307") (name "unconnected-(U1G-VDD_CORE-PadN9)") (class "Default")
      (node (ref "U1") (pin "N9") (pinfunction "VDD_CORE_N9") (pintype "bidirectional"))
    )
    (net (code "308") (name "unconnected-(U1G-VDD_CORE-PadN12)") (class "Default")
      (node (ref "U1") (pin "N12") (pinfunction "VDD_CORE_N12") (pintype "bidirectional"))
    )
    (net (code "309") (name "unconnected-(U1G-VDD_CORE-PadN13)") (class "Default")
      (node (ref "U1") (pin "N13") (pinfunction "VDD_CORE_N13") (pintype "bidirectional"))
    )
    (net (code "310") (name "unconnected-(U1G-VDD_MPU-PadF11)") (class "Default")
      (node (ref "U1") (pin "F11") (pinfunction "VDD_MPU_F11") (pintype "bidirectional"))
    )
    (net (code "311") (name "unconnected-(U1G-VDD_MPU-PadF12)") (class "Default")
      (node (ref "U1") (pin "F12") (pinfunction "VDD_MPU_F12") (pintype "bidirectional"))
    )
    (net (code "312") (name "unconnected-(U1G-VDD_MPU-PadF13)") (class "Default")
      (node (ref "U1") (pin "F13") (pinfunction "VDD_MPU_F13") (pintype "bidirectional"))
    )
    (net (code "313") (name "unconnected-(U1G-VDD_MPU-PadG13)") (class "Default")
      (node (ref "U1") (pin "G13") (pinfunction "VDD_MPU_G13") (pintype "bidirectional"))
    )
    (net (code "314") (name "unconnected-(U1G-VDD_MPU-PadH13)") (class "Default")
      (node (ref "U1") (pin "H13") (pinfunction "VDD_MPU_H13") (pintype "bidirectional"))
    )
    (net (code "315") (name "unconnected-(U1G-VDD_MPU-PadJ13)") (class "Default")
      (node (ref "U1") (pin "J13") (pinfunction "VDD_MPU_J13") (pintype "bidirectional"))
    )
    (net (code "316") (name "unconnected-(U1G-VDD_MPU_MON-PadA2)") (class "Default")
      (node (ref "U1") (pin "A2") (pinfunction "VDD_MPU_MON_A2") (pintype "bidirectional"))
    )
    (net (code "317") (name "unconnected-(U1G-VPP-PadM5)") (class "Default")
      (node (ref "U1") (pin "M5") (pinfunction "VPP_M5") (pintype "bidirectional"))
    )
    (net (code "318") (name "unconnected-(U3-NC-Pad1)") (class "Default")
      (node (ref "U3") (pin "1") (pinfunction "NC_1") (pintype "passive"))
    )
    (net (code "319") (name "unconnected-(U6-ID-Pad3)") (class "Default")
      (node (ref "U6") (pin "3") (pinfunction "ID_3") (pintype "passive"))
    )
    (net (code "320") (name "unconnected-(U6-N.C.-Pad5)") (class "Default")
      (node (ref "U6") (pin "5") (pinfunction "N.C._5") (pintype "no_connect"))
    )
    (net (code "321") (name "unconnected-(U7-N.C.-Pad5)") (class "Default")
      (node (ref "U7") (pin "5") (pinfunction "N.C._5") (pintype "no_connect"))
    )
    (net (code "322") (name "unconnected-(X1-PadOUT_CON)") (class "Default")
      (node (ref "X1") (pin "OUT_CON") (pinfunction "OUT_CON_OUT_CON") (pintype "bidirectional"))
    )
  )
)
